# IN14.net
KiCad netlist of a schematic drawn in Altium Designer
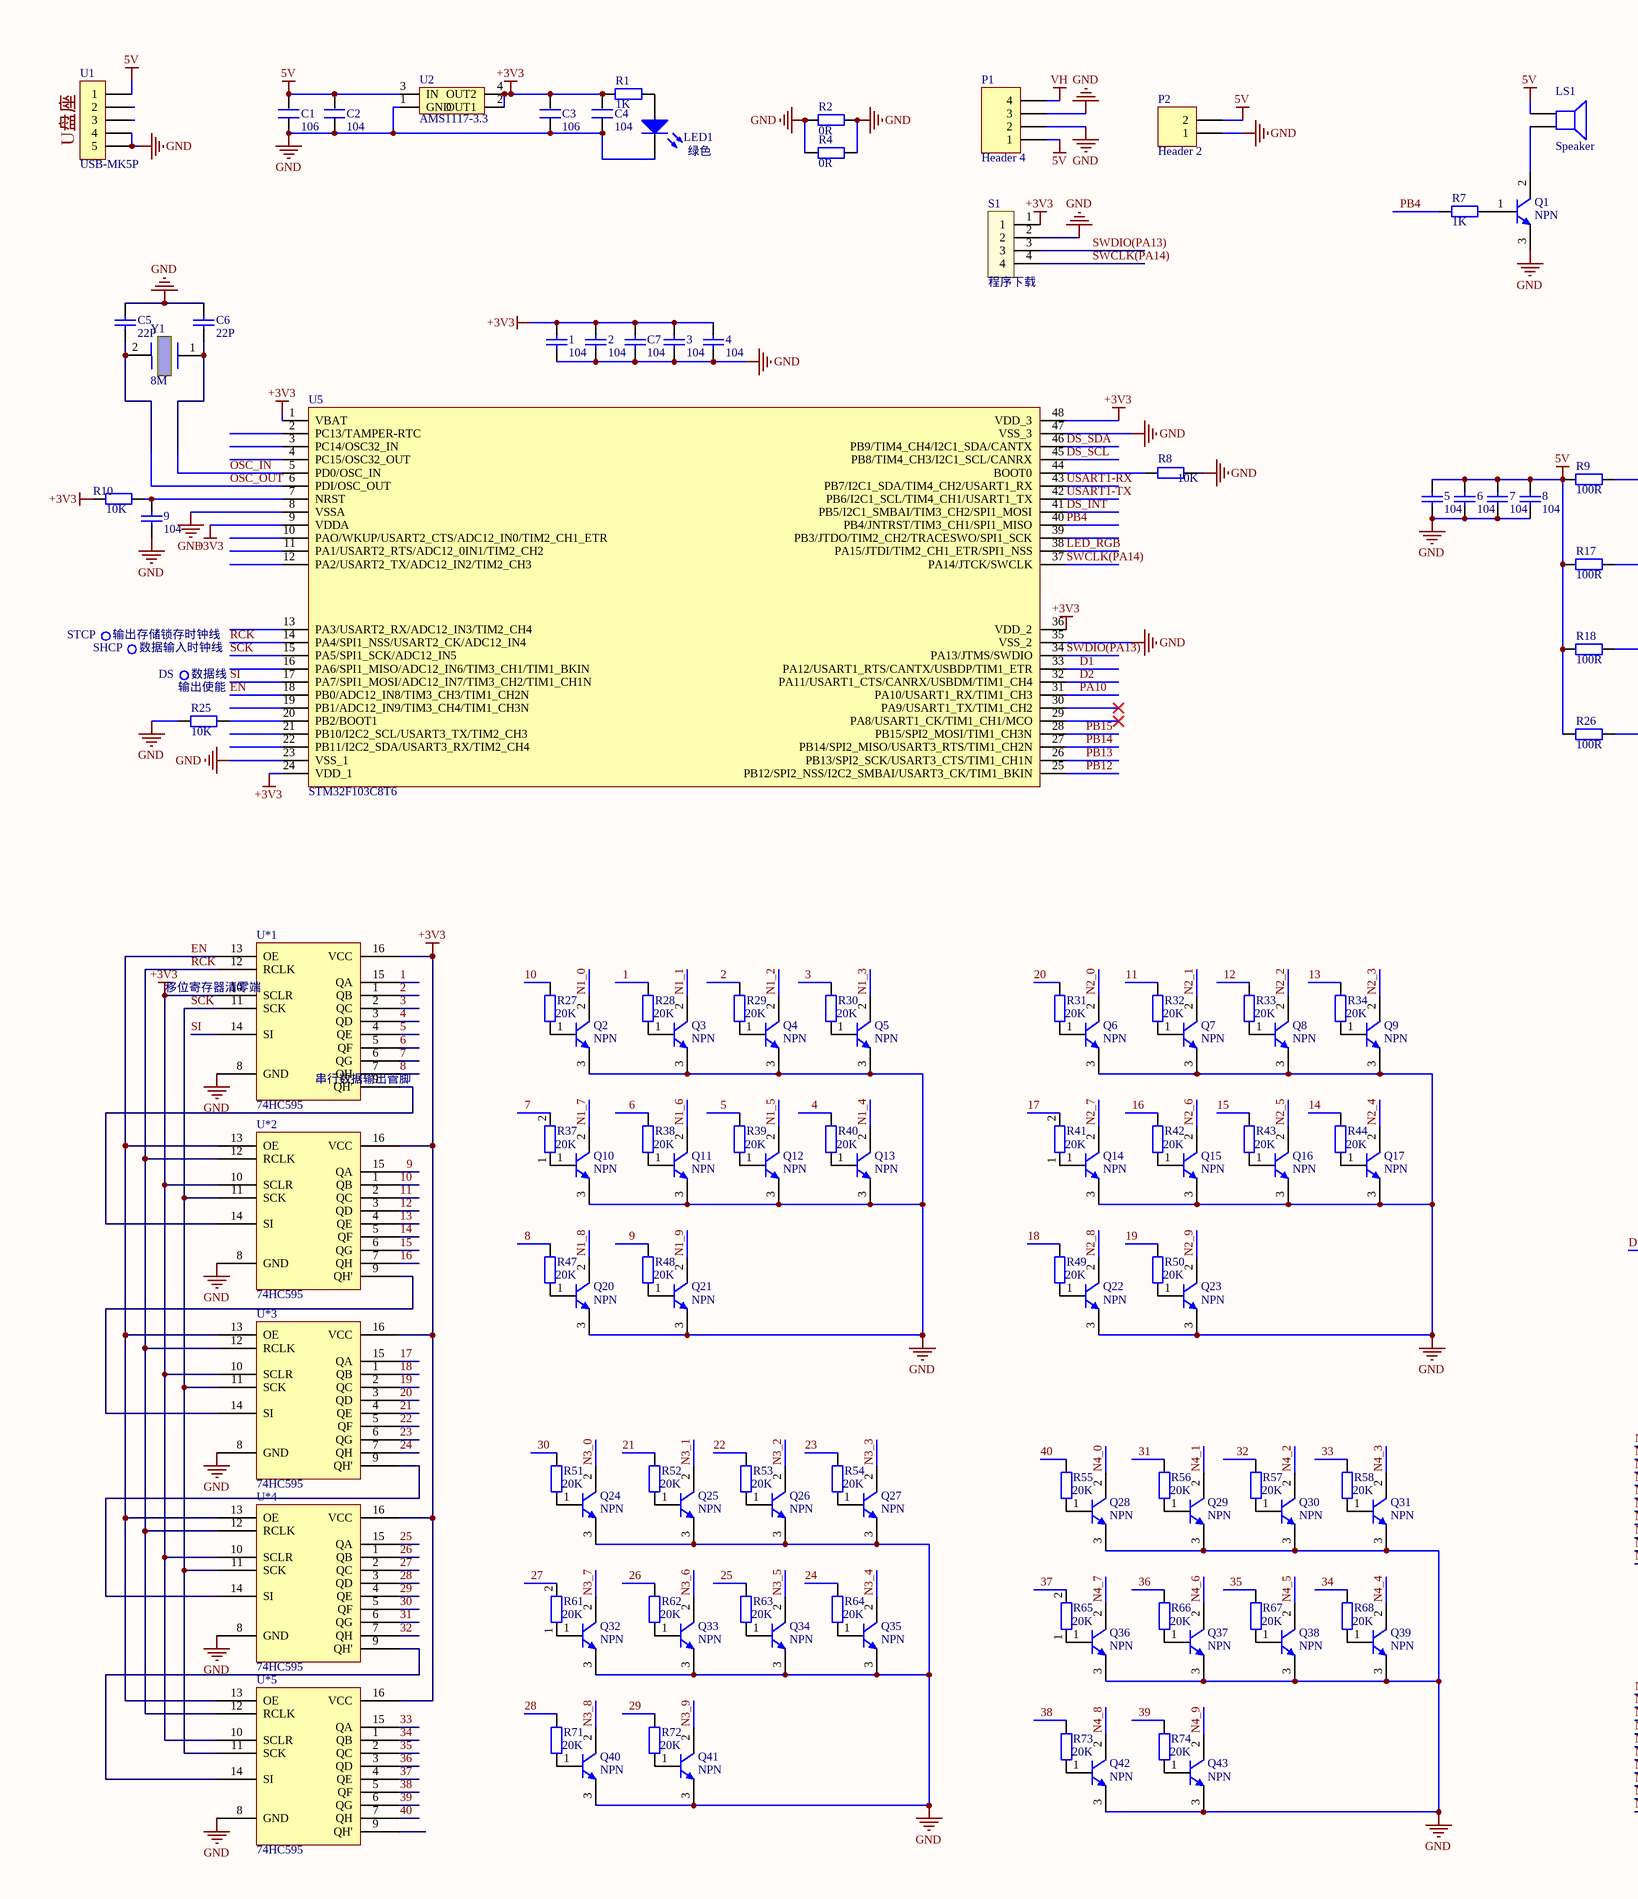
[diagram p0: IN14二灯.SchDoc, left]
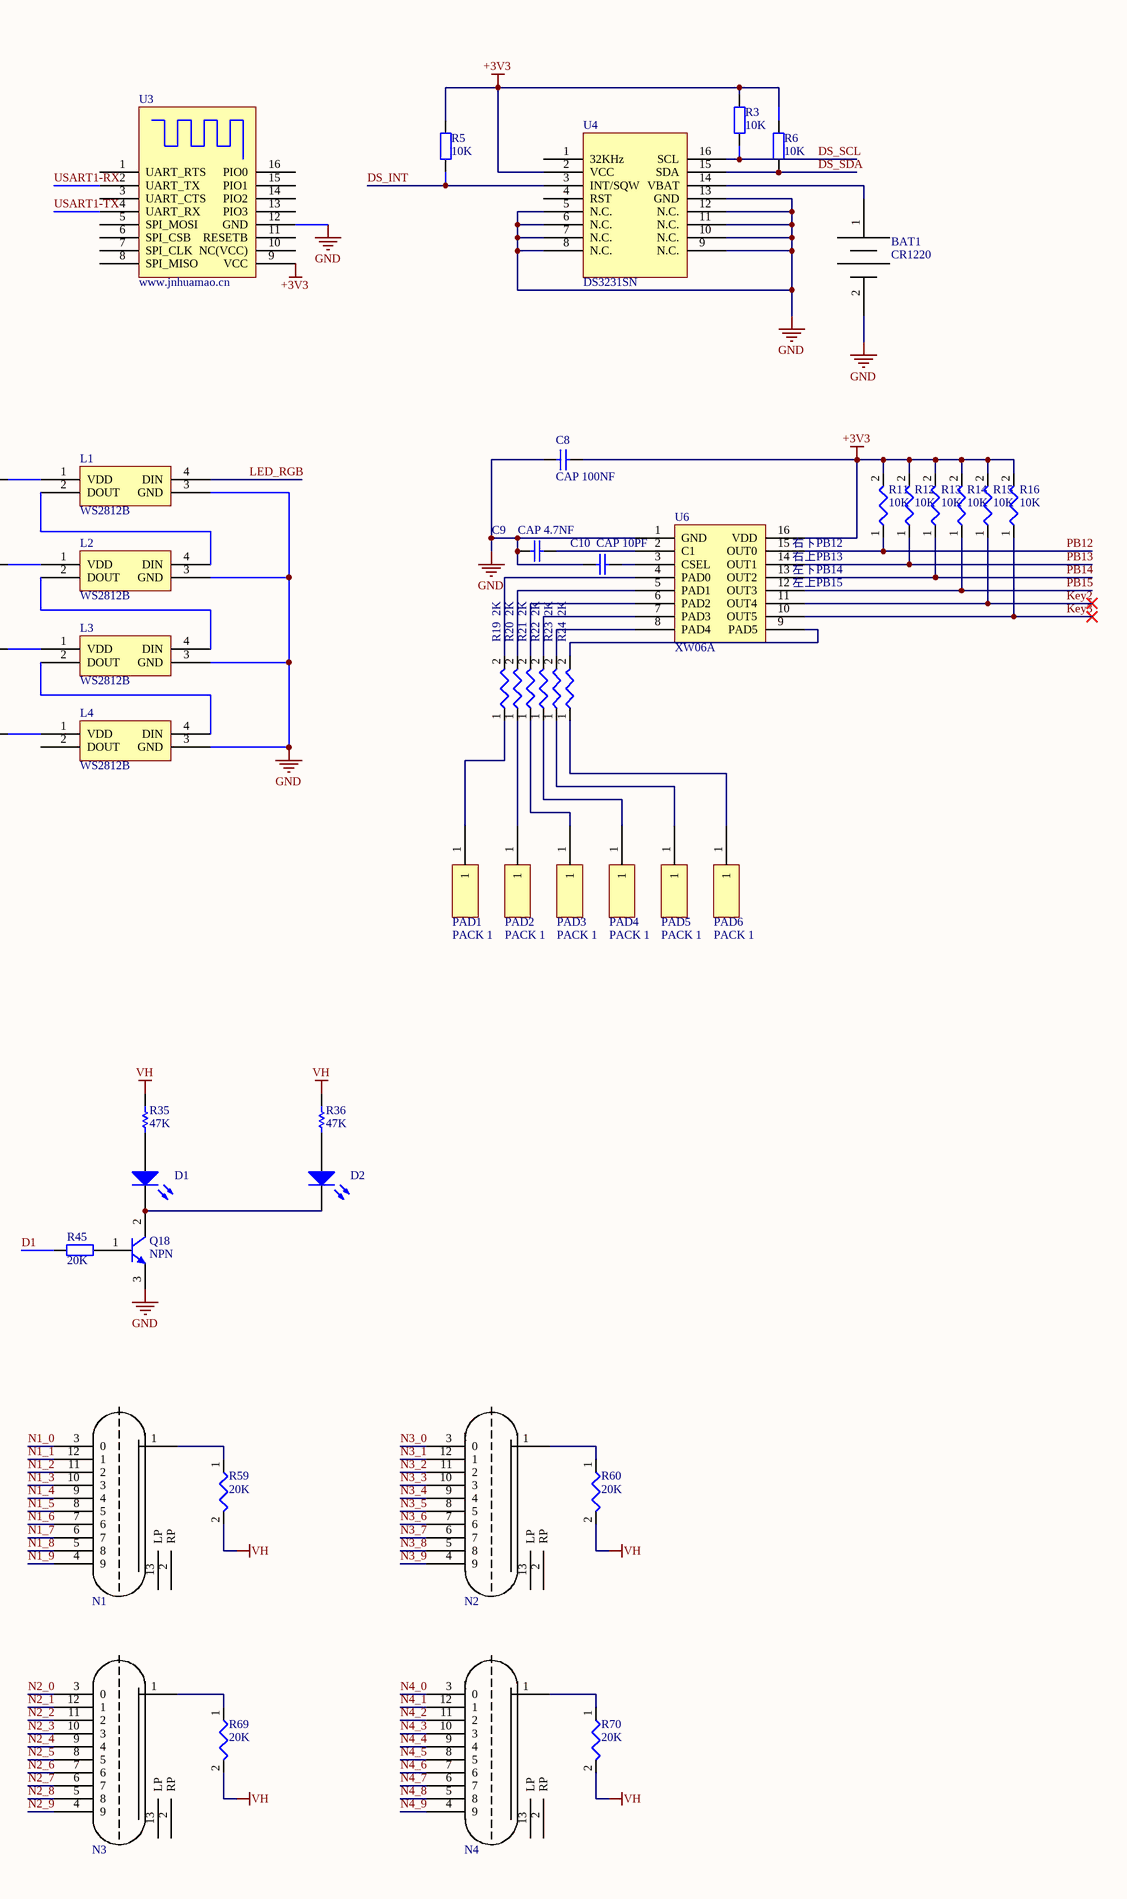
[diagram p1: IN14二灯.SchDoc, right]

(export (version "E")
  (design (tool "Eeschema 10.0.6"))
  (components
    (comp (ref "1")
      (value "104")
      (footprint "0603C")
      (description "无极性电容")
      (fields (field (name "PUBLISHER") "Altium Limited"))
      (libsource (lib "Fszhang") (part "Cap"))
    )
    (comp (ref "2")
      (value "104")
      (footprint "0603C")
      (description "无极性电容")
      (fields (field (name "PUBLISHER") "Altium Limited"))
      (libsource (lib "Fszhang") (part "Cap"))
    )
    (comp (ref "3")
      (value "104")
      (footprint "0603C")
      (description "无极性电容")
      (fields (field (name "PUBLISHER") "Altium Limited"))
      (libsource (lib "Fszhang") (part "Cap"))
    )
    (comp (ref "4")
      (value "104")
      (footprint "0603C")
      (description "无极性电容")
      (fields (field (name "PUBLISHER") "Altium Limited"))
      (libsource (lib "Fszhang") (part "Cap"))
    )
    (comp (ref "5")
      (value "104")
      (footprint "0603C")
      (description "无极性电容")
      (fields (field (name "PUBLISHER") "Altium Limited"))
      (libsource (lib "Fszhang") (part "Cap"))
    )
    (comp (ref "6")
      (value "104")
      (footprint "0603C")
      (description "无极性电容")
      (fields (field (name "PUBLISHER") "Altium Limited"))
      (libsource (lib "Fszhang") (part "Cap"))
    )
    (comp (ref "7")
      (value "104")
      (footprint "0603C")
      (description "无极性电容")
      (fields (field (name "PUBLISHER") "Altium Limited"))
      (libsource (lib "Fszhang") (part "Cap"))
    )
    (comp (ref "8")
      (value "104")
      (footprint "0603C")
      (description "无极性电容")
      (fields (field (name "PUBLISHER") "Altium Limited"))
      (libsource (lib "Fszhang") (part "Cap"))
    )
    (comp (ref "9")
      (value "104")
      (footprint "0603C")
      (description "无极性电容")
      (fields (field (name "PUBLISHER") "Altium Limited"))
      (libsource (lib "Fszhang") (part "Cap"))
    )
    (comp (ref "BAT1") (value "CR1220") (footprint "1220") (libsource (lib "LIGHT") (part "CR1220")))
    (comp (ref "C1") (value "106") (footprint "0805C") (libsource (lib "103驱动2") (part "C")))
    (comp (ref "C2") (value "104") (footprint "0603C") (libsource (lib "103驱动2") (part "C")))
    (comp (ref "C3") (value "106") (footprint "0805C") (libsource (lib "103驱动2") (part "C")))
    (comp (ref "C4") (value "104") (footprint "0603C") (libsource (lib "103驱动2") (part "C")))
    (comp (ref "C5")
      (value "22P")
      (footprint "0603C")
      (description "无极性电容")
      (fields (field (name "PUBLISHER") "Altium Limited"))
      (libsource (lib "Fszhang") (part "Cap"))
    )
    (comp (ref "C6")
      (value "22P")
      (footprint "0603C")
      (description "无极性电容")
      (fields (field (name "PUBLISHER") "Altium Limited"))
      (libsource (lib "Fszhang") (part "Cap"))
    )
    (comp (ref "C7")
      (value "104")
      (footprint "0603C")
      (description "无极性电容")
      (fields (field (name "PUBLISHER") "Altium Limited"))
      (libsource (lib "Fszhang") (part "Cap"))
    )
    (comp (ref "C8") (value "CAP 100NF") (footprint "0603C") (libsource (lib "LIGHT") (part "CAP ?F")))
    (comp (ref "C9") (value "CAP 4.7NF") (footprint "0603C") (libsource (lib "LIGHT") (part "CAP ?F")))
    (comp (ref "C10") (value "CAP 10PF") (footprint "0603C") (libsource (lib "LIGHT") (part "CAP ?F")))
    (comp (ref "D1")
      (value "LED0")
      (footprint "R38")
      (description "Typical INFRARED GaAs LED")
      (fields (field (name "PUBLISHER") "Altium Limited"))
      (libsource (lib "Miscellaneous Devices") (part "LED0"))
    )
    (comp (ref "D2")
      (value "LED0")
      (footprint "R38")
      (description "Typical INFRARED GaAs LED")
      (fields (field (name "PUBLISHER") "Altium Limited"))
      (libsource (lib "Miscellaneous Devices") (part "LED0"))
    )
    (comp (ref "L1") (value "WS2812B") (footprint "WS2812B") (libsource (lib "LIGHT") (part "WS2812B")))
    (comp (ref "L2") (value "WS2812B") (footprint "WS2812B") (libsource (lib "LIGHT") (part "WS2812B")))
    (comp (ref "L3") (value "WS2812B") (footprint "WS2812B") (libsource (lib "LIGHT") (part "WS2812B")))
    (comp (ref "L4") (value "WS2812B") (footprint "WS2812B") (libsource (lib "LIGHT") (part "WS2812B")))
    (comp (ref "LED1")
      (value "绿色")
      (footprint "LED_0805")
      (description "发光二极管")
      (fields (field (name "PUBLISHER") "Altium Limited"))
      (libsource (lib "Fszhang") (part "LED0"))
    )
    (comp (ref "LS1")
      (value "Speaker")
      (footprint "蜂鸣器9*9*5")
      (description "Loudspeaker")
      (fields (field (name "PUBLISHER") "Altium Limited"))
      (libsource (lib "Miscellaneous Devices") (part "Speaker"))
    )
    (comp (ref "N1") (value "IN_14") (footprint "IN14") (libsource (lib "LIGHT") (part "IN_14")))
    (comp (ref "N2") (value "IN_14") (footprint "IN14") (libsource (lib "LIGHT") (part "IN_14")))
    (comp (ref "N3") (value "IN_14") (footprint "IN14") (libsource (lib "LIGHT") (part "IN_14")))
    (comp (ref "N4") (value "IN_14") (footprint "IN14") (libsource (lib "LIGHT") (part "IN_14")))
    (comp (ref "P1")
      (value "Header 4")
      (footprint "XH2.54 4p贴片")
      (description "Header, 4-Pin")
      (fields (field (name "PUBLISHER") "Altium Limited"))
      (libsource (lib "Miscellaneous Connectors") (part "Header 4"))
    )
    (comp (ref "P2")
      (value "Header 2")
      (footprint "XH2.54-2P")
      (description "Header, 2-Pin")
      (fields (field (name "PUBLISHER") "Altium Limited"))
      (libsource (lib "Miscellaneous Connectors") (part "Header 2"))
    )
    (comp (ref "PAD1") (value "PACK 1") (footprint "PACK 1") (libsource (lib "LIGHT") (part "PACK 1")))
    (comp (ref "PAD2") (value "PACK 1") (footprint "PACK 1") (libsource (lib "LIGHT") (part "PACK 1")))
    (comp (ref "PAD3") (value "PACK 1") (footprint "PACK 1") (libsource (lib "LIGHT") (part "PACK 1")))
    (comp (ref "PAD4") (value "PACK 1") (footprint "PACK 1") (libsource (lib "LIGHT") (part "PACK 1")))
    (comp (ref "PAD5") (value "PACK 1") (footprint "PACK 1") (libsource (lib "LIGHT") (part "PACK 1")))
    (comp (ref "PAD6") (value "PACK 1") (footprint "PACK 1") (libsource (lib "LIGHT") (part "PACK 1")))
    (comp (ref "Q1")
      (value "NPN")
      (footprint "LC-SOT-23(SOT-23-3)")
      (description "NPN Bipolar Transistor")
      (fields (field (name "PUBLISHER") "Altium Limited"))
      (libsource (lib "Miscellaneous Devices") (part "NPN"))
    )
    (comp (ref "Q2")
      (value "NPN")
      (footprint "LC-SOT-23(SOT-23-3)")
      (description "NPN Bipolar Transistor")
      (fields (field (name "PUBLISHER") "Altium Limited"))
      (libsource (lib "Miscellaneous Devices") (part "NPN"))
    )
    (comp (ref "Q3")
      (value "NPN")
      (footprint "LC-SOT-23(SOT-23-3)")
      (description "NPN Bipolar Transistor")
      (fields (field (name "PUBLISHER") "Altium Limited"))
      (libsource (lib "Miscellaneous Devices") (part "NPN"))
    )
    (comp (ref "Q4")
      (value "NPN")
      (footprint "LC-SOT-23(SOT-23-3)")
      (description "NPN Bipolar Transistor")
      (fields (field (name "PUBLISHER") "Altium Limited"))
      (libsource (lib "Miscellaneous Devices") (part "NPN"))
    )
    (comp (ref "Q5")
      (value "NPN")
      (footprint "LC-SOT-23(SOT-23-3)")
      (description "NPN Bipolar Transistor")
      (fields (field (name "PUBLISHER") "Altium Limited"))
      (libsource (lib "Miscellaneous Devices") (part "NPN"))
    )
    (comp (ref "Q6")
      (value "NPN")
      (footprint "LC-SOT-23(SOT-23-3)")
      (description "NPN Bipolar Transistor")
      (fields (field (name "PUBLISHER") "Altium Limited"))
      (libsource (lib "Miscellaneous Devices") (part "NPN"))
    )
    (comp (ref "Q7")
      (value "NPN")
      (footprint "LC-SOT-23(SOT-23-3)")
      (description "NPN Bipolar Transistor")
      (fields (field (name "PUBLISHER") "Altium Limited"))
      (libsource (lib "Miscellaneous Devices") (part "NPN"))
    )
    (comp (ref "Q8")
      (value "NPN")
      (footprint "LC-SOT-23(SOT-23-3)")
      (description "NPN Bipolar Transistor")
      (fields (field (name "PUBLISHER") "Altium Limited"))
      (libsource (lib "Miscellaneous Devices") (part "NPN"))
    )
    (comp (ref "Q9")
      (value "NPN")
      (footprint "LC-SOT-23(SOT-23-3)")
      (description "NPN Bipolar Transistor")
      (fields (field (name "PUBLISHER") "Altium Limited"))
      (libsource (lib "Miscellaneous Devices") (part "NPN"))
    )
    (comp (ref "Q10")
      (value "NPN")
      (footprint "LC-SOT-23(SOT-23-3)")
      (description "NPN Bipolar Transistor")
      (fields (field (name "PUBLISHER") "Altium Limited"))
      (libsource (lib "Miscellaneous Devices") (part "NPN"))
    )
    (comp (ref "Q11")
      (value "NPN")
      (footprint "LC-SOT-23(SOT-23-3)")
      (description "NPN Bipolar Transistor")
      (fields (field (name "PUBLISHER") "Altium Limited"))
      (libsource (lib "Miscellaneous Devices") (part "NPN"))
    )
    (comp (ref "Q12")
      (value "NPN")
      (footprint "LC-SOT-23(SOT-23-3)")
      (description "NPN Bipolar Transistor")
      (fields (field (name "PUBLISHER") "Altium Limited"))
      (libsource (lib "Miscellaneous Devices") (part "NPN"))
    )
    (comp (ref "Q13")
      (value "NPN")
      (footprint "LC-SOT-23(SOT-23-3)")
      (description "NPN Bipolar Transistor")
      (fields (field (name "PUBLISHER") "Altium Limited"))
      (libsource (lib "Miscellaneous Devices") (part "NPN"))
    )
    (comp (ref "Q14")
      (value "NPN")
      (footprint "LC-SOT-23(SOT-23-3)")
      (description "NPN Bipolar Transistor")
      (fields (field (name "PUBLISHER") "Altium Limited"))
      (libsource (lib "Miscellaneous Devices") (part "NPN"))
    )
    (comp (ref "Q15")
      (value "NPN")
      (footprint "LC-SOT-23(SOT-23-3)")
      (description "NPN Bipolar Transistor")
      (fields (field (name "PUBLISHER") "Altium Limited"))
      (libsource (lib "Miscellaneous Devices") (part "NPN"))
    )
    (comp (ref "Q16")
      (value "NPN")
      (footprint "LC-SOT-23(SOT-23-3)")
      (description "NPN Bipolar Transistor")
      (fields (field (name "PUBLISHER") "Altium Limited"))
      (libsource (lib "Miscellaneous Devices") (part "NPN"))
    )
    (comp (ref "Q17")
      (value "NPN")
      (footprint "LC-SOT-23(SOT-23-3)")
      (description "NPN Bipolar Transistor")
      (fields (field (name "PUBLISHER") "Altium Limited"))
      (libsource (lib "Miscellaneous Devices") (part "NPN"))
    )
    (comp (ref "Q18")
      (value "NPN")
      (footprint "LC-SOT-23(SOT-23-3)")
      (description "NPN Bipolar Transistor")
      (fields (field (name "PUBLISHER") "Altium Limited"))
      (libsource (lib "Miscellaneous Devices") (part "NPN"))
    )
    (comp (ref "Q20")
      (value "NPN")
      (footprint "LC-SOT-23(SOT-23-3)")
      (description "NPN Bipolar Transistor")
      (fields (field (name "PUBLISHER") "Altium Limited"))
      (libsource (lib "Miscellaneous Devices") (part "NPN"))
    )
    (comp (ref "Q21")
      (value "NPN")
      (footprint "LC-SOT-23(SOT-23-3)")
      (description "NPN Bipolar Transistor")
      (fields (field (name "PUBLISHER") "Altium Limited"))
      (libsource (lib "Miscellaneous Devices") (part "NPN"))
    )
    (comp (ref "Q22")
      (value "NPN")
      (footprint "LC-SOT-23(SOT-23-3)")
      (description "NPN Bipolar Transistor")
      (fields (field (name "PUBLISHER") "Altium Limited"))
      (libsource (lib "Miscellaneous Devices") (part "NPN"))
    )
    (comp (ref "Q23")
      (value "NPN")
      (footprint "LC-SOT-23(SOT-23-3)")
      (description "NPN Bipolar Transistor")
      (fields (field (name "PUBLISHER") "Altium Limited"))
      (libsource (lib "Miscellaneous Devices") (part "NPN"))
    )
    (comp (ref "Q24")
      (value "NPN")
      (footprint "LC-SOT-23(SOT-23-3)")
      (description "NPN Bipolar Transistor")
      (fields (field (name "PUBLISHER") "Altium Limited"))
      (libsource (lib "Miscellaneous Devices") (part "NPN"))
    )
    (comp (ref "Q25")
      (value "NPN")
      (footprint "LC-SOT-23(SOT-23-3)")
      (description "NPN Bipolar Transistor")
      (fields (field (name "PUBLISHER") "Altium Limited"))
      (libsource (lib "Miscellaneous Devices") (part "NPN"))
    )
    (comp (ref "Q26")
      (value "NPN")
      (footprint "LC-SOT-23(SOT-23-3)")
      (description "NPN Bipolar Transistor")
      (fields (field (name "PUBLISHER") "Altium Limited"))
      (libsource (lib "Miscellaneous Devices") (part "NPN"))
    )
    (comp (ref "Q27")
      (value "NPN")
      (footprint "LC-SOT-23(SOT-23-3)")
      (description "NPN Bipolar Transistor")
      (fields (field (name "PUBLISHER") "Altium Limited"))
      (libsource (lib "Miscellaneous Devices") (part "NPN"))
    )
    (comp (ref "Q28")
      (value "NPN")
      (footprint "LC-SOT-23(SOT-23-3)")
      (description "NPN Bipolar Transistor")
      (fields (field (name "PUBLISHER") "Altium Limited"))
      (libsource (lib "Miscellaneous Devices") (part "NPN"))
    )
    (comp (ref "Q29")
      (value "NPN")
      (footprint "LC-SOT-23(SOT-23-3)")
      (description "NPN Bipolar Transistor")
      (fields (field (name "PUBLISHER") "Altium Limited"))
      (libsource (lib "Miscellaneous Devices") (part "NPN"))
    )
    (comp (ref "Q30")
      (value "NPN")
      (footprint "LC-SOT-23(SOT-23-3)")
      (description "NPN Bipolar Transistor")
      (fields (field (name "PUBLISHER") "Altium Limited"))
      (libsource (lib "Miscellaneous Devices") (part "NPN"))
    )
    (comp (ref "Q31")
      (value "NPN")
      (footprint "LC-SOT-23(SOT-23-3)")
      (description "NPN Bipolar Transistor")
      (fields (field (name "PUBLISHER") "Altium Limited"))
      (libsource (lib "Miscellaneous Devices") (part "NPN"))
    )
    (comp (ref "Q32")
      (value "NPN")
      (footprint "LC-SOT-23(SOT-23-3)")
      (description "NPN Bipolar Transistor")
      (fields (field (name "PUBLISHER") "Altium Limited"))
      (libsource (lib "Miscellaneous Devices") (part "NPN"))
    )
    (comp (ref "Q33")
      (value "NPN")
      (footprint "LC-SOT-23(SOT-23-3)")
      (description "NPN Bipolar Transistor")
      (fields (field (name "PUBLISHER") "Altium Limited"))
      (libsource (lib "Miscellaneous Devices") (part "NPN"))
    )
    (comp (ref "Q34")
      (value "NPN")
      (footprint "LC-SOT-23(SOT-23-3)")
      (description "NPN Bipolar Transistor")
      (fields (field (name "PUBLISHER") "Altium Limited"))
      (libsource (lib "Miscellaneous Devices") (part "NPN"))
    )
    (comp (ref "Q35")
      (value "NPN")
      (footprint "LC-SOT-23(SOT-23-3)")
      (description "NPN Bipolar Transistor")
      (fields (field (name "PUBLISHER") "Altium Limited"))
      (libsource (lib "Miscellaneous Devices") (part "NPN"))
    )
    (comp (ref "Q36")
      (value "NPN")
      (footprint "LC-SOT-23(SOT-23-3)")
      (description "NPN Bipolar Transistor")
      (fields (field (name "PUBLISHER") "Altium Limited"))
      (libsource (lib "Miscellaneous Devices") (part "NPN"))
    )
    (comp (ref "Q37")
      (value "NPN")
      (footprint "LC-SOT-23(SOT-23-3)")
      (description "NPN Bipolar Transistor")
      (fields (field (name "PUBLISHER") "Altium Limited"))
      (libsource (lib "Miscellaneous Devices") (part "NPN"))
    )
    (comp (ref "Q38")
      (value "NPN")
      (footprint "LC-SOT-23(SOT-23-3)")
      (description "NPN Bipolar Transistor")
      (fields (field (name "PUBLISHER") "Altium Limited"))
      (libsource (lib "Miscellaneous Devices") (part "NPN"))
    )
    (comp (ref "Q39")
      (value "NPN")
      (footprint "LC-SOT-23(SOT-23-3)")
      (description "NPN Bipolar Transistor")
      (fields (field (name "PUBLISHER") "Altium Limited"))
      (libsource (lib "Miscellaneous Devices") (part "NPN"))
    )
    (comp (ref "Q40")
      (value "NPN")
      (footprint "LC-SOT-23(SOT-23-3)")
      (description "NPN Bipolar Transistor")
      (fields (field (name "PUBLISHER") "Altium Limited"))
      (libsource (lib "Miscellaneous Devices") (part "NPN"))
    )
    (comp (ref "Q41")
      (value "NPN")
      (footprint "LC-SOT-23(SOT-23-3)")
      (description "NPN Bipolar Transistor")
      (fields (field (name "PUBLISHER") "Altium Limited"))
      (libsource (lib "Miscellaneous Devices") (part "NPN"))
    )
    (comp (ref "Q42")
      (value "NPN")
      (footprint "LC-SOT-23(SOT-23-3)")
      (description "NPN Bipolar Transistor")
      (fields (field (name "PUBLISHER") "Altium Limited"))
      (libsource (lib "Miscellaneous Devices") (part "NPN"))
    )
    (comp (ref "Q43")
      (value "NPN")
      (footprint "LC-SOT-23(SOT-23-3)")
      (description "NPN Bipolar Transistor")
      (fields (field (name "PUBLISHER") "Altium Limited"))
      (libsource (lib "Miscellaneous Devices") (part "NPN"))
    )
    (comp (ref "R1")
      (value "1K")
      (footprint "0603R")
      (description "贴片电阻")
      (fields (field (name "PUBLISHER") "Altium Limited"))
      (libsource (lib "") (part "Res1_2"))
    )
    (comp (ref "R2")
      (value "0R")
      (footprint "0603R")
      (description "贴片电阻")
      (fields (field (name "PUBLISHER") "Altium Limited"))
      (libsource (lib "") (part "Res1_1"))
    )
    (comp (ref "R3")
      (value "10K")
      (footprint "0603R")
      (description "贴片电阻")
      (fields (field (name "PUBLISHER") "Altium Limited"))
      (libsource (lib "Fszhang") (part "Res1"))
    )
    (comp (ref "R4")
      (value "0R")
      (footprint "0603R")
      (description "贴片电阻")
      (fields (field (name "PUBLISHER") "Altium Limited"))
      (libsource (lib "") (part "Res1_1"))
    )
    (comp (ref "R5")
      (value "10K")
      (footprint "0603R")
      (description "贴片电阻")
      (fields (field (name "PUBLISHER") "Altium Limited"))
      (libsource (lib "Fszhang") (part "Res1"))
    )
    (comp (ref "R6")
      (value "10K")
      (footprint "0603R")
      (description "贴片电阻")
      (fields (field (name "PUBLISHER") "Altium Limited"))
      (libsource (lib "Fszhang") (part "Res1"))
    )
    (comp (ref "R7")
      (value "1K")
      (footprint "0603R")
      (description "贴片电阻")
      (fields (field (name "PUBLISHER") "Altium Limited"))
      (libsource (lib "") (part "Res1_1"))
    )
    (comp (ref "R8")
      (value "10K")
      (footprint "0603R")
      (description "贴片电阻")
      (fields (field (name "PUBLISHER") "Altium Limited"))
      (libsource (lib "") (part "Res1_1"))
    )
    (comp (ref "R9")
      (value "100R")
      (footprint "0603R")
      (description "贴片电阻")
      (fields (field (name "PUBLISHER") "Altium Limited"))
      (libsource (lib "") (part "Res1_2"))
    )
    (comp (ref "R10")
      (value "10K")
      (footprint "0603R")
      (description "贴片电阻")
      (fields (field (name "PUBLISHER") "Altium Limited"))
      (libsource (lib "") (part "Res1_1"))
    )
    (comp (ref "R11") (value "10K") (footprint "0603R") (libsource (lib "LIGHT") (part "?K")))
    (comp (ref "R12") (value "10K") (footprint "0603R") (libsource (lib "LIGHT") (part "?K")))
    (comp (ref "R13") (value "10K") (footprint "0603R") (libsource (lib "LIGHT") (part "?K")))
    (comp (ref "R14") (value "10K") (footprint "0603R") (libsource (lib "LIGHT") (part "?K")))
    (comp (ref "R15") (value "10K") (footprint "0603R") (libsource (lib "LIGHT") (part "?K")))
    (comp (ref "R16") (value "10K") (footprint "0603R") (libsource (lib "LIGHT") (part "?K")))
    (comp (ref "R17")
      (value "100R")
      (footprint "0603R")
      (description "贴片电阻")
      (fields (field (name "PUBLISHER") "Altium Limited"))
      (libsource (lib "") (part "Res1_2"))
    )
    (comp (ref "R18")
      (value "100R")
      (footprint "0603R")
      (description "贴片电阻")
      (fields (field (name "PUBLISHER") "Altium Limited"))
      (libsource (lib "") (part "Res1_2"))
    )
    (comp (ref "R19") (value "2K") (footprint "0603R") (libsource (lib "LIGHT") (part "?K")))
    (comp (ref "R20") (value "2K") (footprint "0603R") (libsource (lib "LIGHT") (part "?K")))
    (comp (ref "R21") (value "2K") (footprint "0603R") (libsource (lib "LIGHT") (part "?K")))
    (comp (ref "R22") (value "2K") (footprint "0603R") (libsource (lib "LIGHT") (part "?K")))
    (comp (ref "R23") (value "2K") (footprint "0603R") (libsource (lib "LIGHT") (part "?K")))
    (comp (ref "R24") (value "2K") (footprint "0603R") (libsource (lib "LIGHT") (part "?K")))
    (comp (ref "R25")
      (value "10K")
      (footprint "0603R")
      (description "贴片电阻")
      (fields (field (name "PUBLISHER") "Altium Limited"))
      (libsource (lib "") (part "Res1_1"))
    )
    (comp (ref "R26")
      (value "100R")
      (footprint "0603R")
      (description "贴片电阻")
      (fields (field (name "PUBLISHER") "Altium Limited"))
      (libsource (lib "") (part "Res1_2"))
    )
    (comp (ref "R27")
      (value "20K")
      (footprint "0603R")
      (description "贴片电阻")
      (fields (field (name "PUBLISHER") "Altium Limited"))
      (libsource (lib "Fszhang") (part "Res1"))
    )
    (comp (ref "R28")
      (value "20K")
      (footprint "0603R")
      (description "贴片电阻")
      (fields (field (name "PUBLISHER") "Altium Limited"))
      (libsource (lib "Fszhang") (part "Res1"))
    )
    (comp (ref "R29")
      (value "20K")
      (footprint "0603R")
      (description "贴片电阻")
      (fields (field (name "PUBLISHER") "Altium Limited"))
      (libsource (lib "Fszhang") (part "Res1"))
    )
    (comp (ref "R30")
      (value "20K")
      (footprint "0603R")
      (description "贴片电阻")
      (fields (field (name "PUBLISHER") "Altium Limited"))
      (libsource (lib "Fszhang") (part "Res1"))
    )
    (comp (ref "R31")
      (value "20K")
      (footprint "0603R")
      (description "贴片电阻")
      (fields (field (name "PUBLISHER") "Altium Limited"))
      (libsource (lib "Fszhang") (part "Res1"))
    )
    (comp (ref "R32")
      (value "20K")
      (footprint "0603R")
      (description "贴片电阻")
      (fields (field (name "PUBLISHER") "Altium Limited"))
      (libsource (lib "Fszhang") (part "Res1"))
    )
    (comp (ref "R33")
      (value "20K")
      (footprint "0603R")
      (description "贴片电阻")
      (fields (field (name "PUBLISHER") "Altium Limited"))
      (libsource (lib "Fszhang") (part "Res1"))
    )
    (comp (ref "R34")
      (value "20K")
      (footprint "0603R")
      (description "贴片电阻")
      (fields (field (name "PUBLISHER") "Altium Limited"))
      (libsource (lib "Fszhang") (part "Res1"))
    )
    (comp (ref "R35")
      (value "47K")
      (footprint "0805C")
      (description "Resistor")
      (fields (field (name "Comment") "Res1") (field (name "PUBLISHER") "Altium Limited"))
      (libsource (lib "Miscellaneous Devices") (part "Res1"))
    )
    (comp (ref "R36")
      (value "47K")
      (footprint "0805C")
      (description "Resistor")
      (fields (field (name "Comment") "Res1") (field (name "PUBLISHER") "Altium Limited"))
      (libsource (lib "Miscellaneous Devices") (part "Res1"))
    )
    (comp (ref "R37")
      (value "20K")
      (footprint "0603R")
      (description "贴片电阻")
      (fields (field (name "PUBLISHER") "Altium Limited"))
      (libsource (lib "") (part "Res1_3"))
    )
    (comp (ref "R38")
      (value "20K")
      (footprint "0603R")
      (description "贴片电阻")
      (fields (field (name "PUBLISHER") "Altium Limited"))
      (libsource (lib "Fszhang") (part "Res1"))
    )
    (comp (ref "R39")
      (value "20K")
      (footprint "0603R")
      (description "贴片电阻")
      (fields (field (name "PUBLISHER") "Altium Limited"))
      (libsource (lib "Fszhang") (part "Res1"))
    )
    (comp (ref "R40")
      (value "20K")
      (footprint "0603R")
      (description "贴片电阻")
      (fields (field (name "PUBLISHER") "Altium Limited"))
      (libsource (lib "Fszhang") (part "Res1"))
    )
    (comp (ref "R41")
      (value "20K")
      (footprint "0603R")
      (description "贴片电阻")
      (fields (field (name "PUBLISHER") "Altium Limited"))
      (libsource (lib "") (part "Res1_3"))
    )
    (comp (ref "R42")
      (value "20K")
      (footprint "0603R")
      (description "贴片电阻")
      (fields (field (name "PUBLISHER") "Altium Limited"))
      (libsource (lib "Fszhang") (part "Res1"))
    )
    (comp (ref "R43")
      (value "20K")
      (footprint "0603R")
      (description "贴片电阻")
      (fields (field (name "PUBLISHER") "Altium Limited"))
      (libsource (lib "Fszhang") (part "Res1"))
    )
    (comp (ref "R44")
      (value "20K")
      (footprint "0603R")
      (description "贴片电阻")
      (fields (field (name "PUBLISHER") "Altium Limited"))
      (libsource (lib "Fszhang") (part "Res1"))
    )
    (comp (ref "R45")
      (value "20K")
      (footprint "0603R")
      (description "贴片电阻")
      (fields (field (name "PUBLISHER") "Altium Limited"))
      (libsource (lib "") (part "Res1_2"))
    )
    (comp (ref "R47")
      (value "20K")
      (footprint "0603R")
      (description "贴片电阻")
      (fields (field (name "PUBLISHER") "Altium Limited"))
      (libsource (lib "Fszhang") (part "Res1"))
    )
    (comp (ref "R48")
      (value "20K")
      (footprint "0603R")
      (description "贴片电阻")
      (fields (field (name "PUBLISHER") "Altium Limited"))
      (libsource (lib "Fszhang") (part "Res1"))
    )
    (comp (ref "R49")
      (value "20K")
      (footprint "0603R")
      (description "贴片电阻")
      (fields (field (name "PUBLISHER") "Altium Limited"))
      (libsource (lib "Fszhang") (part "Res1"))
    )
    (comp (ref "R50")
      (value "20K")
      (footprint "0603R")
      (description "贴片电阻")
      (fields (field (name "PUBLISHER") "Altium Limited"))
      (libsource (lib "Fszhang") (part "Res1"))
    )
    (comp (ref "R51")
      (value "20K")
      (footprint "0603R")
      (description "贴片电阻")
      (fields (field (name "PUBLISHER") "Altium Limited"))
      (libsource (lib "Fszhang") (part "Res1"))
    )
    (comp (ref "R52")
      (value "20K")
      (footprint "0603R")
      (description "贴片电阻")
      (fields (field (name "PUBLISHER") "Altium Limited"))
      (libsource (lib "Fszhang") (part "Res1"))
    )
    (comp (ref "R53")
      (value "20K")
      (footprint "0603R")
      (description "贴片电阻")
      (fields (field (name "PUBLISHER") "Altium Limited"))
      (libsource (lib "Fszhang") (part "Res1"))
    )
    (comp (ref "R54")
      (value "20K")
      (footprint "0603R")
      (description "贴片电阻")
      (fields (field (name "PUBLISHER") "Altium Limited"))
      (libsource (lib "Fszhang") (part "Res1"))
    )
    (comp (ref "R55")
      (value "20K")
      (footprint "0603R")
      (description "贴片电阻")
      (fields (field (name "PUBLISHER") "Altium Limited"))
      (libsource (lib "Fszhang") (part "Res1"))
    )
    (comp (ref "R56")
      (value "20K")
      (footprint "0603R")
      (description "贴片电阻")
      (fields (field (name "PUBLISHER") "Altium Limited"))
      (libsource (lib "Fszhang") (part "Res1"))
    )
    (comp (ref "R57")
      (value "20K")
      (footprint "0603R")
      (description "贴片电阻")
      (fields (field (name "PUBLISHER") "Altium Limited"))
      (libsource (lib "Fszhang") (part "Res1"))
    )
    (comp (ref "R58")
      (value "20K")
      (footprint "0603R")
      (description "贴片电阻")
      (fields (field (name "PUBLISHER") "Altium Limited"))
      (libsource (lib "Fszhang") (part "Res1"))
    )
    (comp (ref "R59") (value "20K") (footprint "0805C") (libsource (lib "LIGHT") (part "?K")))
    (comp (ref "R60") (value "20K") (footprint "0805C") (libsource (lib "LIGHT") (part "?K")))
    (comp (ref "R61")
      (value "20K")
      (footprint "0603R")
      (description "贴片电阻")
      (fields (field (name "PUBLISHER") "Altium Limited"))
      (libsource (lib "") (part "Res1_3"))
    )
    (comp (ref "R62")
      (value "20K")
      (footprint "0603R")
      (description "贴片电阻")
      (fields (field (name "PUBLISHER") "Altium Limited"))
      (libsource (lib "Fszhang") (part "Res1"))
    )
    (comp (ref "R63")
      (value "20K")
      (footprint "0603R")
      (description "贴片电阻")
      (fields (field (name "PUBLISHER") "Altium Limited"))
      (libsource (lib "Fszhang") (part "Res1"))
    )
    (comp (ref "R64")
      (value "20K")
      (footprint "0603R")
      (description "贴片电阻")
      (fields (field (name "PUBLISHER") "Altium Limited"))
      (libsource (lib "Fszhang") (part "Res1"))
    )
    (comp (ref "R65")
      (value "20K")
      (footprint "0603R")
      (description "贴片电阻")
      (fields (field (name "PUBLISHER") "Altium Limited"))
      (libsource (lib "") (part "Res1_3"))
    )
    (comp (ref "R66")
      (value "20K")
      (footprint "0603R")
      (description "贴片电阻")
      (fields (field (name "PUBLISHER") "Altium Limited"))
      (libsource (lib "Fszhang") (part "Res1"))
    )
    (comp (ref "R67")
      (value "20K")
      (footprint "0603R")
      (description "贴片电阻")
      (fields (field (name "PUBLISHER") "Altium Limited"))
      (libsource (lib "Fszhang") (part "Res1"))
    )
    (comp (ref "R68")
      (value "20K")
      (footprint "0603R")
      (description "贴片电阻")
      (fields (field (name "PUBLISHER") "Altium Limited"))
      (libsource (lib "Fszhang") (part "Res1"))
    )
    (comp (ref "R69") (value "20K") (footprint "0805C") (libsource (lib "LIGHT") (part "?K")))
    (comp (ref "R70") (value "20K") (footprint "0805C") (libsource (lib "LIGHT") (part "?K")))
    (comp (ref "R71")
      (value "20K")
      (footprint "0603R")
      (description "贴片电阻")
      (fields (field (name "PUBLISHER") "Altium Limited"))
      (libsource (lib "Fszhang") (part "Res1"))
    )
    (comp (ref "R72")
      (value "20K")
      (footprint "0603R")
      (description "贴片电阻")
      (fields (field (name "PUBLISHER") "Altium Limited"))
      (libsource (lib "Fszhang") (part "Res1"))
    )
    (comp (ref "R73")
      (value "20K")
      (footprint "0603R")
      (description "贴片电阻")
      (fields (field (name "PUBLISHER") "Altium Limited"))
      (libsource (lib "Fszhang") (part "Res1"))
    )
    (comp (ref "R74")
      (value "20K")
      (footprint "0603R")
      (description "贴片电阻")
      (fields (field (name "PUBLISHER") "Altium Limited"))
      (libsource (lib "Fszhang") (part "Res1"))
    )
    (comp (ref "S1") (value "程序下载") (footprint "HDR1X4") (libsource (lib "ZBC123Schlib1") (part "S-4")))
    (comp (ref "U*1")
      (value "74HC595")
      (footprint "SOP16_M")
      (libsource (lib "74HC595") (part "Component_1"))
    )
    (comp (ref "U*2")
      (value "74HC595")
      (footprint "SOP16_M")
      (libsource (lib "74HC595") (part "Component_1"))
    )
    (comp (ref "U*3")
      (value "74HC595")
      (footprint "SOP16_M")
      (libsource (lib "74HC595") (part "Component_1"))
    )
    (comp (ref "U*4")
      (value "74HC595")
      (footprint "SOP16_M")
      (libsource (lib "74HC595") (part "Component_1"))
    )
    (comp (ref "U*5")
      (value "74HC595")
      (footprint "SOP16_M")
      (libsource (lib "74HC595") (part "Component_1"))
    )
    (comp (ref "U1")
      (value "USB-MK5P")
      (footprint "USB-MK5P")
      (description "Connector")
      (libsource (lib "*") (part "CON5"))
    )
    (comp (ref "U2")
      (value "AMS1117-3.3")
      (footprint "LC-SOT-223 (1117)")
      (libsource (lib "WARSHIP") (part "AMS1117"))
    )
    (comp (ref "U3")
      (value "www.jnhuamao.cn")
      (footprint "HM-05_06_07_11")
      (description "HM bluetooth module HM-05,HM-06,HM-07, HM-11")
      (libsource (lib "HMSoft") (part "HM_05_06_07_11"))
    )
    (comp (ref "U4")
      (value "DS3231SN")
      (footprint "LC-SOP-16_300mil")
      (libsource (lib "LIGHT") (part "DS3231SN"))
    )
    (comp (ref "U5")
      (value "STM32F103C8T6")
      (footprint "LQFP-48_M")
      (libsource (lib "WARSHIP") (part "STM32F103C8T6"))
    )
    (comp (ref "U6") (value "XW06A") (footprint "SO-16_L") (libsource (lib "LIGHT") (part "XW06A")))
    (comp (ref "Y1") (value "8M") (footprint "Y-XTAL T") (libsource (lib "ZBC124Schlib1") (part "JZ")))
  )
  (nets
    (net (code "1") (name "+3V3") (class "Default")
      (node (ref "1") (pin "2") (pinfunction "2_2") (pintype "passive"))
      (node (ref "2") (pin "2") (pinfunction "2_2") (pintype "passive"))
      (node (ref "3") (pin "2") (pinfunction "2_2") (pintype "passive"))
      (node (ref "4") (pin "2") (pinfunction "2_2") (pintype "passive"))
      (node (ref "C3") (pin "2") (pintype "passive"))
      (node (ref "C4") (pin "2") (pintype "passive"))
      (node (ref "C7") (pin "1") (pinfunction "1_1") (pintype "passive"))
      (node (ref "C8") (pin "2") (pinfunction "2_2") (pintype "passive"))
      (node (ref "R1") (pin "1") (pinfunction "1_1") (pintype "passive"))
      (node (ref "R10") (pin "2") (pinfunction "2_2") (pintype "passive"))
      (node (ref "R11") (pin "2") (pinfunction "2_2") (pintype "passive"))
      (node (ref "R12") (pin "2") (pinfunction "2_2") (pintype "passive"))
      (node (ref "R13") (pin "2") (pinfunction "2_2") (pintype "passive"))
      (node (ref "R14") (pin "2") (pinfunction "2_2") (pintype "passive"))
      (node (ref "R15") (pin "2") (pinfunction "2_2") (pintype "passive"))
      (node (ref "R16") (pin "2") (pinfunction "2_2") (pintype "passive"))
      (node (ref "R3") (pin "2") (pinfunction "2_2") (pintype "passive"))
      (node (ref "R5") (pin "2") (pinfunction "2_2") (pintype "passive"))
      (node (ref "R6") (pin "2") (pinfunction "2_2") (pintype "passive"))
      (node (ref "S1") (pin "1") (pinfunction "1_1") (pintype "passive"))
      (node (ref "U*1") (pin "10") (pinfunction "SCLR_10") (pintype "passive"))
      (node (ref "U*1") (pin "16") (pinfunction "VCC_16") (pintype "passive"))
      (node (ref "U*2") (pin "10") (pinfunction "SCLR_10") (pintype "passive"))
      (node (ref "U*2") (pin "16") (pinfunction "VCC_16") (pintype "passive"))
      (node (ref "U*3") (pin "10") (pinfunction "SCLR_10") (pintype "passive"))
      (node (ref "U*3") (pin "16") (pinfunction "VCC_16") (pintype "passive"))
      (node (ref "U*4") (pin "10") (pinfunction "SCLR_10") (pintype "passive"))
      (node (ref "U*4") (pin "16") (pinfunction "VCC_16") (pintype "passive"))
      (node (ref "U*5") (pin "10") (pinfunction "SCLR_10") (pintype "passive"))
      (node (ref "U*5") (pin "16") (pinfunction "VCC_16") (pintype "passive"))
      (node (ref "U2") (pin "2") (pinfunction "OUT1_2") (pintype "passive"))
      (node (ref "U2") (pin "4") (pinfunction "OUT2_4") (pintype "passive"))
      (node (ref "U3") (pin "9") (pinfunction "VCC_9") (pintype "passive"))
      (node (ref "U4") (pin "2") (pinfunction "VCC_2") (pintype "passive"))
      (node (ref "U5") (pin "1") (pinfunction "VBAT_1") (pintype "passive"))
      (node (ref "U5") (pin "24") (pinfunction "VDD_1_24") (pintype "passive"))
      (node (ref "U5") (pin "36") (pinfunction "VDD_2_36") (pintype "passive"))
      (node (ref "U5") (pin "48") (pinfunction "VDD_3_48") (pintype "passive"))
      (node (ref "U5") (pin "9") (pinfunction "VDDA_9") (pintype "passive"))
      (node (ref "U6") (pin "16") (pinfunction "VDD_16") (pintype "passive"))
    )
    (net (code "2") (name "/1") (class "Default")
      (node (ref "R28") (pin "2") (pinfunction "2_2") (pintype "passive"))
      (node (ref "U*1") (pin "15") (pinfunction "QA_15") (pintype "passive"))
    )
    (net (code "3") (name "/2") (class "Default")
      (node (ref "R29") (pin "2") (pinfunction "2_2") (pintype "passive"))
      (node (ref "U*1") (pin "1") (pinfunction "QB_1") (pintype "passive"))
    )
    (net (code "4") (name "/3") (class "Default")
      (node (ref "R30") (pin "2") (pinfunction "2_2") (pintype "passive"))
      (node (ref "U*1") (pin "2") (pinfunction "QC_2") (pintype "passive"))
    )
    (net (code "5") (name "/4") (class "Default")
      (node (ref "R40") (pin "2") (pinfunction "2_2") (pintype "passive"))
      (node (ref "U*1") (pin "3") (pinfunction "QD_3") (pintype "passive"))
    )
    (net (code "6") (name "/5") (class "Default")
      (node (ref "R39") (pin "2") (pinfunction "2_2") (pintype "passive"))
      (node (ref "U*1") (pin "4") (pinfunction "QE_4") (pintype "passive"))
    )
    (net (code "7") (name "/6") (class "Default")
      (node (ref "R38") (pin "2") (pinfunction "2_2") (pintype "passive"))
      (node (ref "U*1") (pin "5") (pinfunction "QF_5") (pintype "passive"))
    )
    (net (code "8") (name "/7") (class "Default")
      (node (ref "R37") (pin "2") (pinfunction "2_2") (pintype "passive"))
      (node (ref "U*1") (pin "6") (pinfunction "QG_6") (pintype "passive"))
    )
    (net (code "9") (name "/8") (class "Default")
      (node (ref "R47") (pin "2") (pinfunction "2_2") (pintype "passive"))
      (node (ref "U*1") (pin "7") (pinfunction "QH_7") (pintype "passive"))
    )
    (net (code "10") (name "/9") (class "Default")
      (node (ref "R48") (pin "2") (pinfunction "2_2") (pintype "passive"))
      (node (ref "U*2") (pin "15") (pinfunction "QA_15") (pintype "passive"))
    )
    (net (code "11") (name "/10") (class "Default")
      (node (ref "R27") (pin "2") (pinfunction "2_2") (pintype "passive"))
      (node (ref "U*2") (pin "1") (pinfunction "QB_1") (pintype "passive"))
    )
    (net (code "12") (name "/11") (class "Default")
      (node (ref "R32") (pin "2") (pinfunction "2_2") (pintype "passive"))
      (node (ref "U*2") (pin "2") (pinfunction "QC_2") (pintype "passive"))
    )
    (net (code "13") (name "/12") (class "Default")
      (node (ref "R33") (pin "2") (pinfunction "2_2") (pintype "passive"))
      (node (ref "U*2") (pin "3") (pinfunction "QD_3") (pintype "passive"))
    )
    (net (code "14") (name "/13") (class "Default")
      (node (ref "R34") (pin "2") (pinfunction "2_2") (pintype "passive"))
      (node (ref "U*2") (pin "4") (pinfunction "QE_4") (pintype "passive"))
    )
    (net (code "15") (name "/14") (class "Default")
      (node (ref "R44") (pin "2") (pinfunction "2_2") (pintype "passive"))
      (node (ref "U*2") (pin "5") (pinfunction "QF_5") (pintype "passive"))
    )
    (net (code "16") (name "/15") (class "Default")
      (node (ref "R43") (pin "2") (pinfunction "2_2") (pintype "passive"))
      (node (ref "U*2") (pin "6") (pinfunction "QG_6") (pintype "passive"))
    )
    (net (code "17") (name "/16") (class "Default")
      (node (ref "R42") (pin "2") (pinfunction "2_2") (pintype "passive"))
      (node (ref "U*2") (pin "7") (pinfunction "QH_7") (pintype "passive"))
    )
    (net (code "18") (name "/17") (class "Default")
      (node (ref "R41") (pin "2") (pinfunction "2_2") (pintype "passive"))
      (node (ref "U*3") (pin "15") (pinfunction "QA_15") (pintype "passive"))
    )
    (net (code "19") (name "/18") (class "Default")
      (node (ref "R49") (pin "2") (pinfunction "2_2") (pintype "passive"))
      (node (ref "U*3") (pin "1") (pinfunction "QB_1") (pintype "passive"))
    )
    (net (code "20") (name "/19") (class "Default")
      (node (ref "R50") (pin "2") (pinfunction "2_2") (pintype "passive"))
      (node (ref "U*3") (pin "2") (pinfunction "QC_2") (pintype "passive"))
    )
    (net (code "21") (name "/20") (class "Default")
      (node (ref "R31") (pin "2") (pinfunction "2_2") (pintype "passive"))
      (node (ref "U*3") (pin "3") (pinfunction "QD_3") (pintype "passive"))
    )
    (net (code "22") (name "/21") (class "Default")
      (node (ref "R52") (pin "2") (pinfunction "2_2") (pintype "passive"))
      (node (ref "U*3") (pin "4") (pinfunction "QE_4") (pintype "passive"))
    )
    (net (code "23") (name "/22") (class "Default")
      (node (ref "R53") (pin "2") (pinfunction "2_2") (pintype "passive"))
      (node (ref "U*3") (pin "5") (pinfunction "QF_5") (pintype "passive"))
    )
    (net (code "24") (name "/23") (class "Default")
      (node (ref "R54") (pin "2") (pinfunction "2_2") (pintype "passive"))
      (node (ref "U*3") (pin "6") (pinfunction "QG_6") (pintype "passive"))
    )
    (net (code "25") (name "/24") (class "Default")
      (node (ref "R64") (pin "2") (pinfunction "2_2") (pintype "passive"))
      (node (ref "U*3") (pin "7") (pinfunction "QH_7") (pintype "passive"))
    )
    (net (code "26") (name "/25") (class "Default")
      (node (ref "R63") (pin "2") (pinfunction "2_2") (pintype "passive"))
      (node (ref "U*4") (pin "15") (pinfunction "QA_15") (pintype "passive"))
    )
    (net (code "27") (name "/26") (class "Default")
      (node (ref "R62") (pin "2") (pinfunction "2_2") (pintype "passive"))
      (node (ref "U*4") (pin "1") (pinfunction "QB_1") (pintype "passive"))
    )
    (net (code "28") (name "/27") (class "Default")
      (node (ref "R61") (pin "2") (pinfunction "2_2") (pintype "passive"))
      (node (ref "U*4") (pin "2") (pinfunction "QC_2") (pintype "passive"))
    )
    (net (code "29") (name "/28") (class "Default")
      (node (ref "R71") (pin "2") (pinfunction "2_2") (pintype "passive"))
      (node (ref "U*4") (pin "3") (pinfunction "QD_3") (pintype "passive"))
    )
    (net (code "30") (name "/29") (class "Default")
      (node (ref "R72") (pin "2") (pinfunction "2_2") (pintype "passive"))
      (node (ref "U*4") (pin "4") (pinfunction "QE_4") (pintype "passive"))
    )
    (net (code "31") (name "/30") (class "Default")
      (node (ref "R51") (pin "2") (pinfunction "2_2") (pintype "passive"))
      (node (ref "U*4") (pin "5") (pinfunction "QF_5") (pintype "passive"))
    )
    (net (code "32") (name "/31") (class "Default")
      (node (ref "R56") (pin "2") (pinfunction "2_2") (pintype "passive"))
      (node (ref "U*4") (pin "6") (pinfunction "QG_6") (pintype "passive"))
    )
    (net (code "33") (name "/32") (class "Default")
      (node (ref "R57") (pin "2") (pinfunction "2_2") (pintype "passive"))
      (node (ref "U*4") (pin "7") (pinfunction "QH_7") (pintype "passive"))
    )
    (net (code "34") (name "/33") (class "Default")
      (node (ref "R58") (pin "2") (pinfunction "2_2") (pintype "passive"))
      (node (ref "U*5") (pin "15") (pinfunction "QA_15") (pintype "passive"))
    )
    (net (code "35") (name "/34") (class "Default")
      (node (ref "R68") (pin "2") (pinfunction "2_2") (pintype "passive"))
      (node (ref "U*5") (pin "1") (pinfunction "QB_1") (pintype "passive"))
    )
    (net (code "36") (name "/35") (class "Default")
      (node (ref "R67") (pin "2") (pinfunction "2_2") (pintype "passive"))
      (node (ref "U*5") (pin "2") (pinfunction "QC_2") (pintype "passive"))
    )
    (net (code "37") (name "/36") (class "Default")
      (node (ref "R66") (pin "2") (pinfunction "2_2") (pintype "passive"))
      (node (ref "U*5") (pin "3") (pinfunction "QD_3") (pintype "passive"))
    )
    (net (code "38") (name "/37") (class "Default")
      (node (ref "R65") (pin "2") (pinfunction "2_2") (pintype "passive"))
      (node (ref "U*5") (pin "4") (pinfunction "QE_4") (pintype "passive"))
    )
    (net (code "39") (name "/38") (class "Default")
      (node (ref "R73") (pin "2") (pinfunction "2_2") (pintype "passive"))
      (node (ref "U*5") (pin "5") (pinfunction "QF_5") (pintype "passive"))
    )
    (net (code "40") (name "/39") (class "Default")
      (node (ref "R74") (pin "2") (pinfunction "2_2") (pintype "passive"))
      (node (ref "U*5") (pin "6") (pinfunction "QG_6") (pintype "passive"))
    )
    (net (code "41") (name "/40") (class "Default")
      (node (ref "R55") (pin "2") (pinfunction "2_2") (pintype "passive"))
      (node (ref "U*5") (pin "7") (pinfunction "QH_7") (pintype "passive"))
    )
    (net (code "42") (name "/D1") (class "Default")
      (node (ref "R45") (pin "1") (pinfunction "1_1") (pintype "passive"))
      (node (ref "U5") (pin "33") (pinfunction "PA12/USART1_RTS/CANTX/USBDP/TIM1_ETR_33") (pintype "passive"))
    )
    (net (code "43") (name "/D2") (class "Default")
      (node (ref "U5") (pin "32") (pinfunction "PA11/USART1_CTS/CANRX/USBDM/TIM1_CH4_32") (pintype "passive"))
    )
    (net (code "44") (name "/DS_INT") (class "Default")
      (node (ref "R5") (pin "1") (pinfunction "1_1") (pintype "passive"))
      (node (ref "U4") (pin "3") (pinfunction "INT/SQW_3") (pintype "passive"))
      (node (ref "U5") (pin "41") (pinfunction "PB5/I2C1_SMBAI/TIM3_CH2/SPI1_MOSI_41") (pintype "passive"))
    )
    (net (code "45") (name "/DS_SCL") (class "Default")
      (node (ref "R3") (pin "1") (pinfunction "1_1") (pintype "passive"))
      (node (ref "U4") (pin "16") (pinfunction "SCL_16") (pintype "passive"))
      (node (ref "U5") (pin "45") (pinfunction "PB8/TIM4_CH3/I2C1_SCL/CANRX_45") (pintype "passive"))
    )
    (net (code "46") (name "/DS_SDA") (class "Default")
      (node (ref "R6") (pin "1") (pinfunction "1_1") (pintype "passive"))
      (node (ref "U4") (pin "15") (pinfunction "SDA_15") (pintype "passive"))
      (node (ref "U5") (pin "46") (pinfunction "PB9/TIM4_CH4/I2C1_SDA/CANTX_46") (pintype "passive"))
    )
    (net (code "47") (name "/EN") (class "Default")
      (node (ref "U*1") (pin "13") (pinfunction "OE_13") (pintype "passive"))
      (node (ref "U*2") (pin "13") (pinfunction "OE_13") (pintype "passive"))
      (node (ref "U*3") (pin "13") (pinfunction "OE_13") (pintype "passive"))
      (node (ref "U*4") (pin "13") (pinfunction "OE_13") (pintype "passive"))
      (node (ref "U*5") (pin "13") (pinfunction "OE_13") (pintype "passive"))
      (node (ref "U5") (pin "18") (pinfunction "PB0/ADC12_IN8/TIM3_CH3/TIM1_CH2N_18") (pintype "passive"))
    )
    (net (code "48") (name "/Key2") (class "Default")
      (node (ref "R15") (pin "1") (pinfunction "1_1") (pintype "passive"))
      (node (ref "U6") (pin "11") (pinfunction "OUT4_11") (pintype "passive"))
    )
    (net (code "49") (name "/Key3") (class "Default")
      (node (ref "R16") (pin "1") (pinfunction "1_1") (pintype "passive"))
      (node (ref "U6") (pin "10") (pinfunction "OUT5_10") (pintype "passive"))
    )
    (net (code "50") (name "/LED_RGB") (class "Default")
      (node (ref "L1") (pin "4") (pinfunction "DIN_4") (pintype "passive"))
      (node (ref "U5") (pin "38") (pinfunction "PA15/JTDI/TIM2_CH1_ETR/SPI1_NSS_38") (pintype "passive"))
    )
    (net (code "51") (name "/N1_0") (class "Default")
      (node (ref "N1") (pin "3") (pinfunction "0_3") (pintype "passive"))
      (node (ref "Q2") (pin "2") (pinfunction "B_2") (pintype "passive"))
    )
    (net (code "52") (name "/N1_1") (class "Default")
      (node (ref "N1") (pin "12") (pinfunction "1_12") (pintype "passive"))
      (node (ref "Q3") (pin "2") (pinfunction "B_2") (pintype "passive"))
    )
    (net (code "53") (name "/N1_2") (class "Default")
      (node (ref "N1") (pin "11") (pinfunction "2_11") (pintype "passive"))
      (node (ref "Q4") (pin "2") (pinfunction "B_2") (pintype "passive"))
    )
    (net (code "54") (name "/N1_3") (class "Default")
      (node (ref "N1") (pin "10") (pinfunction "3_10") (pintype "passive"))
      (node (ref "Q5") (pin "2") (pinfunction "B_2") (pintype "passive"))
    )
    (net (code "55") (name "/N1_4") (class "Default")
      (node (ref "N1") (pin "9") (pinfunction "4_9") (pintype "passive"))
      (node (ref "Q13") (pin "2") (pinfunction "B_2") (pintype "passive"))
    )
    (net (code "56") (name "/N1_5") (class "Default")
      (node (ref "N1") (pin "8") (pinfunction "5_8") (pintype "passive"))
      (node (ref "Q12") (pin "2") (pinfunction "B_2") (pintype "passive"))
    )
    (net (code "57") (name "/N1_6") (class "Default")
      (node (ref "N1") (pin "7") (pinfunction "6_7") (pintype "passive"))
      (node (ref "Q11") (pin "2") (pinfunction "B_2") (pintype "passive"))
    )
    (net (code "58") (name "/N1_7") (class "Default")
      (node (ref "N1") (pin "6") (pinfunction "7_6") (pintype "passive"))
      (node (ref "Q10") (pin "2") (pinfunction "B_2") (pintype "passive"))
    )
    (net (code "59") (name "/N1_8") (class "Default")
      (node (ref "N1") (pin "5") (pinfunction "8_5") (pintype "passive"))
      (node (ref "Q20") (pin "2") (pinfunction "B_2") (pintype "passive"))
    )
    (net (code "60") (name "/N1_9") (class "Default")
      (node (ref "N1") (pin "4") (pinfunction "9_4") (pintype "passive"))
      (node (ref "Q21") (pin "2") (pinfunction "B_2") (pintype "passive"))
    )
    (net (code "61") (name "/N2_0") (class "Default")
      (node (ref "N3") (pin "3") (pinfunction "0_3") (pintype "passive"))
      (node (ref "Q6") (pin "2") (pinfunction "B_2") (pintype "passive"))
    )
    (net (code "62") (name "/N2_1") (class "Default")
      (node (ref "N3") (pin "12") (pinfunction "1_12") (pintype "passive"))
      (node (ref "Q7") (pin "2") (pinfunction "B_2") (pintype "passive"))
    )
    (net (code "63") (name "/N2_2") (class "Default")
      (node (ref "N3") (pin "11") (pinfunction "2_11") (pintype "passive"))
      (node (ref "Q8") (pin "2") (pinfunction "B_2") (pintype "passive"))
    )
    (net (code "64") (name "/N2_3") (class "Default")
      (node (ref "N3") (pin "10") (pinfunction "3_10") (pintype "passive"))
      (node (ref "Q9") (pin "2") (pinfunction "B_2") (pintype "passive"))
    )
    (net (code "65") (name "/N2_4") (class "Default")
      (node (ref "N3") (pin "9") (pinfunction "4_9") (pintype "passive"))
      (node (ref "Q17") (pin "2") (pinfunction "B_2") (pintype "passive"))
    )
    (net (code "66") (name "/N2_5") (class "Default")
      (node (ref "N3") (pin "8") (pinfunction "5_8") (pintype "passive"))
      (node (ref "Q16") (pin "2") (pinfunction "B_2") (pintype "passive"))
    )
    (net (code "67") (name "/N2_6") (class "Default")
      (node (ref "N3") (pin "7") (pinfunction "6_7") (pintype "passive"))
      (node (ref "Q15") (pin "2") (pinfunction "B_2") (pintype "passive"))
    )
    (net (code "68") (name "/N2_7") (class "Default")
      (node (ref "N3") (pin "6") (pinfunction "7_6") (pintype "passive"))
      (node (ref "Q14") (pin "2") (pinfunction "B_2") (pintype "passive"))
    )
    (net (code "69") (name "/N2_8") (class "Default")
      (node (ref "N3") (pin "5") (pinfunction "8_5") (pintype "passive"))
      (node (ref "Q22") (pin "2") (pinfunction "B_2") (pintype "passive"))
    )
    (net (code "70") (name "/N2_9") (class "Default")
      (node (ref "N3") (pin "4") (pinfunction "9_4") (pintype "passive"))
      (node (ref "Q23") (pin "2") (pinfunction "B_2") (pintype "passive"))
    )
    (net (code "71") (name "/N3_0") (class "Default")
      (node (ref "N2") (pin "3") (pinfunction "0_3") (pintype "passive"))
      (node (ref "Q24") (pin "2") (pinfunction "B_2") (pintype "passive"))
    )
    (net (code "72") (name "/N3_1") (class "Default")
      (node (ref "N2") (pin "12") (pinfunction "1_12") (pintype "passive"))
      (node (ref "Q25") (pin "2") (pinfunction "B_2") (pintype "passive"))
    )
    (net (code "73") (name "/N3_2") (class "Default")
      (node (ref "N2") (pin "11") (pinfunction "2_11") (pintype "passive"))
      (node (ref "Q26") (pin "2") (pinfunction "B_2") (pintype "passive"))
    )
    (net (code "74") (name "/N3_3") (class "Default")
      (node (ref "N2") (pin "10") (pinfunction "3_10") (pintype "passive"))
      (node (ref "Q27") (pin "2") (pinfunction "B_2") (pintype "passive"))
    )
    (net (code "75") (name "/N3_4") (class "Default")
      (node (ref "N2") (pin "9") (pinfunction "4_9") (pintype "passive"))
      (node (ref "Q35") (pin "2") (pinfunction "B_2") (pintype "passive"))
    )
    (net (code "76") (name "/N3_5") (class "Default")
      (node (ref "N2") (pin "8") (pinfunction "5_8") (pintype "passive"))
      (node (ref "Q34") (pin "2") (pinfunction "B_2") (pintype "passive"))
    )
    (net (code "77") (name "/N3_6") (class "Default")
      (node (ref "N2") (pin "7") (pinfunction "6_7") (pintype "passive"))
      (node (ref "Q33") (pin "2") (pinfunction "B_2") (pintype "passive"))
    )
    (net (code "78") (name "/N3_7") (class "Default")
      (node (ref "N2") (pin "6") (pinfunction "7_6") (pintype "passive"))
      (node (ref "Q32") (pin "2") (pinfunction "B_2") (pintype "passive"))
    )
    (net (code "79") (name "/N3_8") (class "Default")
      (node (ref "N2") (pin "5") (pinfunction "8_5") (pintype "passive"))
      (node (ref "Q40") (pin "2") (pinfunction "B_2") (pintype "passive"))
    )
    (net (code "80") (name "/N3_9") (class "Default")
      (node (ref "N2") (pin "4") (pinfunction "9_4") (pintype "passive"))
      (node (ref "Q41") (pin "2") (pinfunction "B_2") (pintype "passive"))
    )
    (net (code "81") (name "/N4_0") (class "Default")
      (node (ref "N4") (pin "3") (pinfunction "0_3") (pintype "passive"))
      (node (ref "Q28") (pin "2") (pinfunction "B_2") (pintype "passive"))
    )
    (net (code "82") (name "/N4_1") (class "Default")
      (node (ref "N4") (pin "12") (pinfunction "1_12") (pintype "passive"))
      (node (ref "Q29") (pin "2") (pinfunction "B_2") (pintype "passive"))
    )
    (net (code "83") (name "/N4_2") (class "Default")
      (node (ref "N4") (pin "11") (pinfunction "2_11") (pintype "passive"))
      (node (ref "Q30") (pin "2") (pinfunction "B_2") (pintype "passive"))
    )
    (net (code "84") (name "/N4_3") (class "Default")
      (node (ref "N4") (pin "10") (pinfunction "3_10") (pintype "passive"))
      (node (ref "Q31") (pin "2") (pinfunction "B_2") (pintype "passive"))
    )
    (net (code "85") (name "/N4_4") (class "Default")
      (node (ref "N4") (pin "9") (pinfunction "4_9") (pintype "passive"))
      (node (ref "Q39") (pin "2") (pinfunction "B_2") (pintype "passive"))
    )
    (net (code "86") (name "/N4_5") (class "Default")
      (node (ref "N4") (pin "8") (pinfunction "5_8") (pintype "passive"))
      (node (ref "Q38") (pin "2") (pinfunction "B_2") (pintype "passive"))
    )
    (net (code "87") (name "/N4_6") (class "Default")
      (node (ref "N4") (pin "7") (pinfunction "6_7") (pintype "passive"))
      (node (ref "Q37") (pin "2") (pinfunction "B_2") (pintype "passive"))
    )
    (net (code "88") (name "/N4_7") (class "Default")
      (node (ref "N4") (pin "6") (pinfunction "7_6") (pintype "passive"))
      (node (ref "Q36") (pin "2") (pinfunction "B_2") (pintype "passive"))
    )
    (net (code "89") (name "/N4_8") (class "Default")
      (node (ref "N4") (pin "5") (pinfunction "8_5") (pintype "passive"))
      (node (ref "Q42") (pin "2") (pinfunction "B_2") (pintype "passive"))
    )
    (net (code "90") (name "/N4_9") (class "Default")
      (node (ref "N4") (pin "4") (pinfunction "9_4") (pintype "passive"))
      (node (ref "Q43") (pin "2") (pinfunction "B_2") (pintype "passive"))
    )
    (net (code "91") (name "/OSC_IN") (class "Default")
      (node (ref "C6") (pin "1") (pinfunction "1_1") (pintype "passive"))
      (node (ref "U5") (pin "5") (pinfunction "PD0/OSC_IN_5") (pintype "passive"))
      (node (ref "Y1") (pin "1") (pinfunction "1_1") (pintype "passive"))
    )
    (net (code "92") (name "/OSC_OUT") (class "Default")
      (node (ref "C5") (pin "1") (pinfunction "1_1") (pintype "passive"))
      (node (ref "U5") (pin "6") (pinfunction "PDI/OSC_OUT_6") (pintype "passive"))
      (node (ref "Y1") (pin "2") (pinfunction "2_2") (pintype "passive"))
    )
    (net (code "93") (name "/PA10") (class "Default")
      (node (ref "U5") (pin "31") (pinfunction "PA10/USART1_RX/TIM1_CH3_31") (pintype "passive"))
    )
    (net (code "94") (name "/PB4") (class "Default")
      (node (ref "R7") (pin "2") (pinfunction "2_2") (pintype "passive"))
      (node (ref "U5") (pin "40") (pinfunction "PB4/JNTRST/TIM3_CH1/SPI1_MISO_40") (pintype "passive"))
    )
    (net (code "95") (name "/PB12") (class "Default")
      (node (ref "R11") (pin "1") (pinfunction "1_1") (pintype "passive"))
      (node (ref "U5") (pin "25") (pinfunction "PB12/SPI2_NSS/I2C2_SMBAI/USART3_CK/TIM1_BKIN_25") (pintype "passive"))
      (node (ref "U6") (pin "15") (pinfunction "OUT0_15") (pintype "passive"))
    )
    (net (code "96") (name "/PB13") (class "Default")
      (node (ref "R12") (pin "1") (pinfunction "1_1") (pintype "passive"))
      (node (ref "U5") (pin "26") (pinfunction "PB13/SPI2_SCK/USART3_CTS/TIM1_CH1N_26") (pintype "passive"))
      (node (ref "U6") (pin "14") (pinfunction "OUT1_14") (pintype "passive"))
    )
    (net (code "97") (name "/PB14") (class "Default")
      (node (ref "R13") (pin "1") (pinfunction "1_1") (pintype "passive"))
      (node (ref "U5") (pin "27") (pinfunction "PB14/SPI2_MISO/USART3_RTS/TIM1_CH2N_27") (pintype "passive"))
      (node (ref "U6") (pin "13") (pinfunction "OUT2_13") (pintype "passive"))
    )
    (net (code "98") (name "/PB15") (class "Default")
      (node (ref "R14") (pin "1") (pinfunction "1_1") (pintype "passive"))
      (node (ref "U5") (pin "28") (pinfunction "PB15/SPI2_MOSI/TIM1_CH3N_28") (pintype "passive"))
      (node (ref "U6") (pin "12") (pinfunction "OUT3_12") (pintype "passive"))
    )
    (net (code "99") (name "/RCK") (class "Default")
      (node (ref "U*1") (pin "12") (pinfunction "RCLK_12") (pintype "passive"))
      (node (ref "U*2") (pin "12") (pinfunction "RCLK_12") (pintype "passive"))
      (node (ref "U*3") (pin "12") (pinfunction "RCLK_12") (pintype "passive"))
      (node (ref "U*4") (pin "12") (pinfunction "RCLK_12") (pintype "passive"))
      (node (ref "U*5") (pin "12") (pinfunction "RCLK_12") (pintype "passive"))
      (node (ref "U5") (pin "14") (pinfunction "PA4/SPI1_NSS/USART2_CK/ADC12_IN4_14") (pintype "passive"))
    )
    (net (code "100") (name "/SCK") (class "Default")
      (node (ref "U*1") (pin "11") (pinfunction "SCK_11") (pintype "passive"))
      (node (ref "U*2") (pin "11") (pinfunction "SCK_11") (pintype "passive"))
      (node (ref "U*3") (pin "11") (pinfunction "SCK_11") (pintype "passive"))
      (node (ref "U*4") (pin "11") (pinfunction "SCK_11") (pintype "passive"))
      (node (ref "U*5") (pin "11") (pinfunction "SCK_11") (pintype "passive"))
      (node (ref "U5") (pin "15") (pinfunction "PA5/SPI1_SCK/ADC12_IN5_15") (pintype "passive"))
    )
    (net (code "101") (name "/SI") (class "Default")
      (node (ref "U*1") (pin "14") (pinfunction "SI_14") (pintype "passive"))
      (node (ref "U5") (pin "17") (pinfunction "PA7/SPI1_MOSI/ADC12_IN7/TIM3_CH2/TIM1_CH1N_17") (pintype "passive"))
    )
    (net (code "102") (name "/SWCLK(PA14)") (class "Default")
      (node (ref "S1") (pin "4") (pinfunction "4_4") (pintype "passive"))
      (node (ref "U5") (pin "37") (pinfunction "PA14/JTCK/SWCLK_37") (pintype "passive"))
    )
    (net (code "103") (name "/SWDIO(PA13)") (class "Default")
      (node (ref "S1") (pin "3") (pinfunction "3_3") (pintype "passive"))
      (node (ref "U5") (pin "34") (pinfunction "PA13/JTMS/SWDIO_34") (pintype "passive"))
    )
    (net (code "104") (name "/USART1-RX") (class "Default")
      (node (ref "U3") (pin "2") (pinfunction "UART_TX_2") (pintype "passive"))
      (node (ref "U5") (pin "43") (pinfunction "PB7/I2C1_SDA/TIM4_CH2/USART1_RX_43") (pintype "passive"))
    )
    (net (code "105") (name "/USART1-TX") (class "Default")
      (node (ref "U3") (pin "4") (pinfunction "UART_RX_4") (pintype "passive"))
      (node (ref "U5") (pin "42") (pinfunction "PB6/I2C1_SCL/TIM4_CH1/USART1_TX_42") (pintype "passive"))
    )
    (net (code "106") (name "5V") (class "Default")
      (node (ref "5") (pin "2") (pinfunction "2_2") (pintype "passive"))
      (node (ref "6") (pin "2") (pinfunction "2_2") (pintype "passive"))
      (node (ref "7") (pin "2") (pinfunction "2_2") (pintype "passive"))
      (node (ref "8") (pin "2") (pinfunction "2_2") (pintype "passive"))
      (node (ref "C1") (pin "2") (pintype "passive"))
      (node (ref "C2") (pin "2") (pintype "passive"))
      (node (ref "LS1") (pin "1") (pinfunction "1_1") (pintype "passive"))
      (node (ref "P1") (pin "1") (pinfunction "1_1") (pintype "passive"))
      (node (ref "P2") (pin "2") (pinfunction "2_2") (pintype "passive"))
      (node (ref "R17") (pin "1") (pinfunction "1_1") (pintype "passive"))
      (node (ref "R18") (pin "1") (pinfunction "1_1") (pintype "passive"))
      (node (ref "R26") (pin "1") (pinfunction "1_1") (pintype "passive"))
      (node (ref "R9") (pin "1") (pinfunction "1_1") (pintype "passive"))
      (node (ref "U1") (pin "1") (pinfunction "1_1") (pintype "passive"))
      (node (ref "U2") (pin "3") (pinfunction "IN_3") (pintype "passive"))
    )
    (net (code "107") (name "GND") (class "Default")
      (node (ref "1") (pin "1") (pinfunction "1_1") (pintype "passive"))
      (node (ref "2") (pin "1") (pinfunction "1_1") (pintype "passive"))
      (node (ref "3") (pin "1") (pinfunction "1_1") (pintype "passive"))
      (node (ref "4") (pin "1") (pinfunction "1_1") (pintype "passive"))
      (node (ref "5") (pin "1") (pinfunction "1_1") (pintype "passive"))
      (node (ref "6") (pin "1") (pinfunction "1_1") (pintype "passive"))
      (node (ref "7") (pin "1") (pinfunction "1_1") (pintype "passive"))
      (node (ref "8") (pin "1") (pinfunction "1_1") (pintype "passive"))
      (node (ref "9") (pin "2") (pinfunction "2_2") (pintype "passive"))
      (node (ref "BAT1") (pin "2") (pinfunction "2_2") (pintype "passive"))
      (node (ref "C1") (pin "1") (pintype "passive"))
      (node (ref "C10") (pin "1") (pinfunction "1_1") (pintype "passive"))
      (node (ref "C2") (pin "1") (pintype "passive"))
      (node (ref "C3") (pin "1") (pintype "passive"))
      (node (ref "C4") (pin "1") (pintype "passive"))
      (node (ref "C5") (pin "2") (pinfunction "2_2") (pintype "passive"))
      (node (ref "C6") (pin "2") (pinfunction "2_2") (pintype "passive"))
      (node (ref "C7") (pin "2") (pinfunction "2_2") (pintype "passive"))
      (node (ref "C8") (pin "1") (pinfunction "1_1") (pintype "passive"))
      (node (ref "C9") (pin "1") (pinfunction "1_1") (pintype "passive"))
      (node (ref "L1") (pin "3") (pinfunction "GND_3") (pintype "passive"))
      (node (ref "L2") (pin "3") (pinfunction "GND_3") (pintype "passive"))
      (node (ref "L3") (pin "3") (pinfunction "GND_3") (pintype "passive"))
      (node (ref "L4") (pin "3") (pinfunction "GND_3") (pintype "passive"))
      (node (ref "LED1") (pin "2") (pinfunction "K_2") (pintype "passive"))
      (node (ref "P1") (pin "2") (pinfunction "2_2") (pintype "passive"))
      (node (ref "P1") (pin "3") (pinfunction "3_3") (pintype "passive"))
      (node (ref "P2") (pin "1") (pinfunction "1_1") (pintype "passive"))
      (node (ref "Q1") (pin "3") (pinfunction "C_3") (pintype "passive"))
      (node (ref "Q10") (pin "3") (pinfunction "C_3") (pintype "passive"))
      (node (ref "Q11") (pin "3") (pinfunction "C_3") (pintype "passive"))
      (node (ref "Q12") (pin "3") (pinfunction "C_3") (pintype "passive"))
      (node (ref "Q13") (pin "3") (pinfunction "C_3") (pintype "passive"))
      (node (ref "Q14") (pin "3") (pinfunction "C_3") (pintype "passive"))
      (node (ref "Q15") (pin "3") (pinfunction "C_3") (pintype "passive"))
      (node (ref "Q16") (pin "3") (pinfunction "C_3") (pintype "passive"))
      (node (ref "Q17") (pin "3") (pinfunction "C_3") (pintype "passive"))
      (node (ref "Q18") (pin "3") (pinfunction "C_3") (pintype "passive"))
      (node (ref "Q2") (pin "3") (pinfunction "C_3") (pintype "passive"))
      (node (ref "Q20") (pin "3") (pinfunction "C_3") (pintype "passive"))
      (node (ref "Q21") (pin "3") (pinfunction "C_3") (pintype "passive"))
      (node (ref "Q22") (pin "3") (pinfunction "C_3") (pintype "passive"))
      (node (ref "Q23") (pin "3") (pinfunction "C_3") (pintype "passive"))
      (node (ref "Q24") (pin "3") (pinfunction "C_3") (pintype "passive"))
      (node (ref "Q25") (pin "3") (pinfunction "C_3") (pintype "passive"))
      (node (ref "Q26") (pin "3") (pinfunction "C_3") (pintype "passive"))
      (node (ref "Q27") (pin "3") (pinfunction "C_3") (pintype "passive"))
      (node (ref "Q28") (pin "3") (pinfunction "C_3") (pintype "passive"))
      (node (ref "Q29") (pin "3") (pinfunction "C_3") (pintype "passive"))
      (node (ref "Q3") (pin "3") (pinfunction "C_3") (pintype "passive"))
      (node (ref "Q30") (pin "3") (pinfunction "C_3") (pintype "passive"))
      (node (ref "Q31") (pin "3") (pinfunction "C_3") (pintype "passive"))
      (node (ref "Q32") (pin "3") (pinfunction "C_3") (pintype "passive"))
      (node (ref "Q33") (pin "3") (pinfunction "C_3") (pintype "passive"))
      (node (ref "Q34") (pin "3") (pinfunction "C_3") (pintype "passive"))
      (node (ref "Q35") (pin "3") (pinfunction "C_3") (pintype "passive"))
      (node (ref "Q36") (pin "3") (pinfunction "C_3") (pintype "passive"))
      (node (ref "Q37") (pin "3") (pinfunction "C_3") (pintype "passive"))
      (node (ref "Q38") (pin "3") (pinfunction "C_3") (pintype "passive"))
      (node (ref "Q39") (pin "3") (pinfunction "C_3") (pintype "passive"))
      (node (ref "Q4") (pin "3") (pinfunction "C_3") (pintype "passive"))
      (node (ref "Q40") (pin "3") (pinfunction "C_3") (pintype "passive"))
      (node (ref "Q41") (pin "3") (pinfunction "C_3") (pintype "passive"))
      (node (ref "Q42") (pin "3") (pinfunction "C_3") (pintype "passive"))
      (node (ref "Q43") (pin "3") (pinfunction "C_3") (pintype "passive"))
      (node (ref "Q5") (pin "3") (pinfunction "C_3") (pintype "passive"))
      (node (ref "Q6") (pin "3") (pinfunction "C_3") (pintype "passive"))
      (node (ref "Q7") (pin "3") (pinfunction "C_3") (pintype "passive"))
      (node (ref "Q8") (pin "3") (pinfunction "C_3") (pintype "passive"))
      (node (ref "Q9") (pin "3") (pinfunction "C_3") (pintype "passive"))
      (node (ref "R2") (pin "1") (pinfunction "1_1") (pintype "passive"))
      (node (ref "R2") (pin "2") (pinfunction "2_2") (pintype "passive"))
      (node (ref "R25") (pin "2") (pinfunction "2_2") (pintype "passive"))
      (node (ref "R4") (pin "1") (pinfunction "1_1") (pintype "passive"))
      (node (ref "R4") (pin "2") (pinfunction "2_2") (pintype "passive"))
      (node (ref "R8") (pin "1") (pinfunction "1_1") (pintype "passive"))
      (node (ref "S1") (pin "2") (pinfunction "2_2") (pintype "passive"))
      (node (ref "U*1") (pin "8") (pinfunction "GND_8") (pintype "passive"))
      (node (ref "U*2") (pin "8") (pinfunction "GND_8") (pintype "passive"))
      (node (ref "U*3") (pin "8") (pinfunction "GND_8") (pintype "passive"))
      (node (ref "U*4") (pin "8") (pinfunction "GND_8") (pintype "passive"))
      (node (ref "U*5") (pin "8") (pinfunction "GND_8") (pintype "passive"))
      (node (ref "U1") (pin "4") (pinfunction "4_4") (pintype "passive"))
      (node (ref "U1") (pin "5") (pinfunction "5_5") (pintype "passive"))
      (node (ref "U2") (pin "1") (pinfunction "GND_1") (pintype "passive"))
      (node (ref "U3") (pin "12") (pinfunction "GND_12") (pintype "passive"))
      (node (ref "U4") (pin "10") (pinfunction "N.C._10") (pintype "passive"))
      (node (ref "U4") (pin "11") (pinfunction "N.C._11") (pintype "passive"))
      (node (ref "U4") (pin "12") (pinfunction "N.C._12") (pintype "passive"))
      (node (ref "U4") (pin "13") (pinfunction "GND_13") (pintype "passive"))
      (node (ref "U4") (pin "5") (pinfunction "N.C._5") (pintype "passive"))
      (node (ref "U4") (pin "6") (pinfunction "N.C._6") (pintype "passive"))
      (node (ref "U4") (pin "7") (pinfunction "N.C._7") (pintype "passive"))
      (node (ref "U4") (pin "8") (pinfunction "N.C._8") (pintype "passive"))
      (node (ref "U4") (pin "9") (pinfunction "N.C._9") (pintype "passive"))
      (node (ref "U5") (pin "23") (pinfunction "VSS_1_23") (pintype "passive"))
      (node (ref "U5") (pin "35") (pinfunction "VSS_2_35") (pintype "passive"))
      (node (ref "U5") (pin "47") (pinfunction "VSS_3_47") (pintype "passive"))
      (node (ref "U5") (pin "8") (pinfunction "VSSA_8") (pintype "passive"))
      (node (ref "U6") (pin "1") (pinfunction "GND_1") (pintype "passive"))
    )
    (net (code "108") (name "Net-(D1-A)") (class "Default")
      (node (ref "D1") (pin "1") (pinfunction "A_1") (pintype "passive"))
      (node (ref "R35") (pin "2") (pinfunction "2_2") (pintype "passive"))
    )
    (net (code "109") (name "Net-(D1-K)") (class "Default")
      (node (ref "D1") (pin "2") (pinfunction "K_2") (pintype "passive"))
      (node (ref "D2") (pin "2") (pinfunction "K_2") (pintype "passive"))
      (node (ref "Q18") (pin "2") (pinfunction "B_2") (pintype "passive"))
    )
    (net (code "110") (name "Net-(D2-A)") (class "Default")
      (node (ref "D2") (pin "1") (pinfunction "A_1") (pintype "passive"))
      (node (ref "R36") (pin "2") (pinfunction "2_2") (pintype "passive"))
    )
    (net (code "111") (name "Net-(L1-DOUT)") (class "Default")
      (node (ref "L1") (pin "2") (pinfunction "DOUT_2") (pintype "passive"))
      (node (ref "L2") (pin "4") (pinfunction "DIN_4") (pintype "passive"))
    )
    (net (code "112") (name "Net-(L1-VDD)") (class "Default")
      (node (ref "L1") (pin "1") (pinfunction "VDD_1") (pintype "passive"))
      (node (ref "R9") (pin "2") (pinfunction "2_2") (pintype "passive"))
    )
    (net (code "113") (name "Net-(L2-DOUT)") (class "Default")
      (node (ref "L2") (pin "2") (pinfunction "DOUT_2") (pintype "passive"))
      (node (ref "L3") (pin "4") (pinfunction "DIN_4") (pintype "passive"))
    )
    (net (code "114") (name "Net-(L2-VDD)") (class "Default")
      (node (ref "L2") (pin "1") (pinfunction "VDD_1") (pintype "passive"))
      (node (ref "R17") (pin "2") (pinfunction "2_2") (pintype "passive"))
    )
    (net (code "115") (name "Net-(L3-DOUT)") (class "Default")
      (node (ref "L3") (pin "2") (pinfunction "DOUT_2") (pintype "passive"))
      (node (ref "L4") (pin "4") (pinfunction "DIN_4") (pintype "passive"))
    )
    (net (code "116") (name "Net-(L3-VDD)") (class "Default")
      (node (ref "L3") (pin "1") (pinfunction "VDD_1") (pintype "passive"))
      (node (ref "R18") (pin "2") (pinfunction "2_2") (pintype "passive"))
    )
    (net (code "117") (name "Net-(L4-VDD)") (class "Default")
      (node (ref "L4") (pin "1") (pinfunction "VDD_1") (pintype "passive"))
      (node (ref "R26") (pin "2") (pinfunction "2_2") (pintype "passive"))
    )
    (net (code "118") (name "Net-(LED1-A)") (class "Default")
      (node (ref "LED1") (pin "1") (pinfunction "A_1") (pintype "passive"))
      (node (ref "R1") (pin "2") (pinfunction "2_2") (pintype "passive"))
    )
    (net (code "119") (name "Net-(N1-VCC)") (class "Default")
      (node (ref "N1") (pin "1") (pinfunction "VCC_1") (pintype "passive"))
      (node (ref "R59") (pin "1") (pinfunction "1_1") (pintype "passive"))
    )
    (net (code "120") (name "Net-(N2-VCC)") (class "Default")
      (node (ref "N2") (pin "1") (pinfunction "VCC_1") (pintype "passive"))
      (node (ref "R60") (pin "1") (pinfunction "1_1") (pintype "passive"))
    )
    (net (code "121") (name "Net-(N3-VCC)") (class "Default")
      (node (ref "N3") (pin "1") (pinfunction "VCC_1") (pintype "passive"))
      (node (ref "R69") (pin "1") (pinfunction "1_1") (pintype "passive"))
    )
    (net (code "122") (name "Net-(N4-VCC)") (class "Default")
      (node (ref "N4") (pin "1") (pinfunction "VCC_1") (pintype "passive"))
      (node (ref "R70") (pin "1") (pinfunction "1_1") (pintype "passive"))
    )
    (net (code "123") (name "Net-(PAD1-Pad1)") (class "Default")
      (node (ref "PAD1") (pin "1") (pinfunction "1_1") (pintype "passive"))
      (node (ref "R19") (pin "1") (pinfunction "1_1") (pintype "passive"))
    )
    (net (code "124") (name "Net-(PAD2-Pad1)") (class "Default")
      (node (ref "PAD2") (pin "1") (pinfunction "1_1") (pintype "passive"))
      (node (ref "R20") (pin "1") (pinfunction "1_1") (pintype "passive"))
    )
    (net (code "125") (name "Net-(PAD3-Pad1)") (class "Default")
      (node (ref "PAD3") (pin "1") (pinfunction "1_1") (pintype "passive"))
      (node (ref "R21") (pin "1") (pinfunction "1_1") (pintype "passive"))
    )
    (net (code "126") (name "Net-(PAD4-Pad1)") (class "Default")
      (node (ref "PAD4") (pin "1") (pinfunction "1_1") (pintype "passive"))
      (node (ref "R22") (pin "1") (pinfunction "1_1") (pintype "passive"))
    )
    (net (code "127") (name "Net-(PAD5-Pad1)") (class "Default")
      (node (ref "PAD5") (pin "1") (pinfunction "1_1") (pintype "passive"))
      (node (ref "R23") (pin "1") (pinfunction "1_1") (pintype "passive"))
    )
    (net (code "128") (name "Net-(PAD6-Pad1)") (class "Default")
      (node (ref "PAD6") (pin "1") (pinfunction "1_1") (pintype "passive"))
      (node (ref "R24") (pin "1") (pinfunction "1_1") (pintype "passive"))
    )
    (net (code "129") (name "Net-(Q1-B)") (class "Default")
      (node (ref "LS1") (pin "2") (pinfunction "2_2") (pintype "passive"))
      (node (ref "Q1") (pin "2") (pinfunction "B_2") (pintype "passive"))
    )
    (net (code "130") (name "Net-(Q1-E)") (class "Default")
      (node (ref "Q1") (pin "1") (pinfunction "E_1") (pintype "passive"))
      (node (ref "R7") (pin "1") (pinfunction "1_1") (pintype "passive"))
    )
    (net (code "131") (name "Net-(Q2-E)") (class "Default")
      (node (ref "Q2") (pin "1") (pinfunction "E_1") (pintype "passive"))
      (node (ref "R27") (pin "1") (pinfunction "1_1") (pintype "passive"))
    )
    (net (code "132") (name "Net-(Q3-E)") (class "Default")
      (node (ref "Q3") (pin "1") (pinfunction "E_1") (pintype "passive"))
      (node (ref "R28") (pin "1") (pinfunction "1_1") (pintype "passive"))
    )
    (net (code "133") (name "Net-(Q4-E)") (class "Default")
      (node (ref "Q4") (pin "1") (pinfunction "E_1") (pintype "passive"))
      (node (ref "R29") (pin "1") (pinfunction "1_1") (pintype "passive"))
    )
    (net (code "134") (name "Net-(Q5-E)") (class "Default")
      (node (ref "Q5") (pin "1") (pinfunction "E_1") (pintype "passive"))
      (node (ref "R30") (pin "1") (pinfunction "1_1") (pintype "passive"))
    )
    (net (code "135") (name "Net-(Q6-E)") (class "Default")
      (node (ref "Q6") (pin "1") (pinfunction "E_1") (pintype "passive"))
      (node (ref "R31") (pin "1") (pinfunction "1_1") (pintype "passive"))
    )
    (net (code "136") (name "Net-(Q7-E)") (class "Default")
      (node (ref "Q7") (pin "1") (pinfunction "E_1") (pintype "passive"))
      (node (ref "R32") (pin "1") (pinfunction "1_1") (pintype "passive"))
    )
    (net (code "137") (name "Net-(Q8-E)") (class "Default")
      (node (ref "Q8") (pin "1") (pinfunction "E_1") (pintype "passive"))
      (node (ref "R33") (pin "1") (pinfunction "1_1") (pintype "passive"))
    )
    (net (code "138") (name "Net-(Q9-E)") (class "Default")
      (node (ref "Q9") (pin "1") (pinfunction "E_1") (pintype "passive"))
      (node (ref "R34") (pin "1") (pinfunction "1_1") (pintype "passive"))
    )
    (net (code "139") (name "Net-(Q10-E)") (class "Default")
      (node (ref "Q10") (pin "1") (pinfunction "E_1") (pintype "passive"))
      (node (ref "R37") (pin "1") (pinfunction "1_1") (pintype "passive"))
    )
    (net (code "140") (name "Net-(Q11-E)") (class "Default")
      (node (ref "Q11") (pin "1") (pinfunction "E_1") (pintype "passive"))
      (node (ref "R38") (pin "1") (pinfunction "1_1") (pintype "passive"))
    )
    (net (code "141") (name "Net-(Q12-E)") (class "Default")
      (node (ref "Q12") (pin "1") (pinfunction "E_1") (pintype "passive"))
      (node (ref "R39") (pin "1") (pinfunction "1_1") (pintype "passive"))
    )
    (net (code "142") (name "Net-(Q13-E)") (class "Default")
      (node (ref "Q13") (pin "1") (pinfunction "E_1") (pintype "passive"))
      (node (ref "R40") (pin "1") (pinfunction "1_1") (pintype "passive"))
    )
    (net (code "143") (name "Net-(Q14-E)") (class "Default")
      (node (ref "Q14") (pin "1") (pinfunction "E_1") (pintype "passive"))
      (node (ref "R41") (pin "1") (pinfunction "1_1") (pintype "passive"))
    )
    (net (code "144") (name "Net-(Q15-E)") (class "Default")
      (node (ref "Q15") (pin "1") (pinfunction "E_1") (pintype "passive"))
      (node (ref "R42") (pin "1") (pinfunction "1_1") (pintype "passive"))
    )
    (net (code "145") (name "Net-(Q16-E)") (class "Default")
      (node (ref "Q16") (pin "1") (pinfunction "E_1") (pintype "passive"))
      (node (ref "R43") (pin "1") (pinfunction "1_1") (pintype "passive"))
    )
    (net (code "146") (name "Net-(Q17-E)") (class "Default")
      (node (ref "Q17") (pin "1") (pinfunction "E_1") (pintype "passive"))
      (node (ref "R44") (pin "1") (pinfunction "1_1") (pintype "passive"))
    )
    (net (code "147") (name "Net-(Q18-E)") (class "Default")
      (node (ref "Q18") (pin "1") (pinfunction "E_1") (pintype "passive"))
      (node (ref "R45") (pin "2") (pinfunction "2_2") (pintype "passive"))
    )
    (net (code "148") (name "Net-(Q20-E)") (class "Default")
      (node (ref "Q20") (pin "1") (pinfunction "E_1") (pintype "passive"))
      (node (ref "R47") (pin "1") (pinfunction "1_1") (pintype "passive"))
    )
    (net (code "149") (name "Net-(Q21-E)") (class "Default")
      (node (ref "Q21") (pin "1") (pinfunction "E_1") (pintype "passive"))
      (node (ref "R48") (pin "1") (pinfunction "1_1") (pintype "passive"))
    )
    (net (code "150") (name "Net-(Q22-E)") (class "Default")
      (node (ref "Q22") (pin "1") (pinfunction "E_1") (pintype "passive"))
      (node (ref "R49") (pin "1") (pinfunction "1_1") (pintype "passive"))
    )
    (net (code "151") (name "Net-(Q23-E)") (class "Default")
      (node (ref "Q23") (pin "1") (pinfunction "E_1") (pintype "passive"))
      (node (ref "R50") (pin "1") (pinfunction "1_1") (pintype "passive"))
    )
    (net (code "152") (name "Net-(Q24-E)") (class "Default")
      (node (ref "Q24") (pin "1") (pinfunction "E_1") (pintype "passive"))
      (node (ref "R51") (pin "1") (pinfunction "1_1") (pintype "passive"))
    )
    (net (code "153") (name "Net-(Q25-E)") (class "Default")
      (node (ref "Q25") (pin "1") (pinfunction "E_1") (pintype "passive"))
      (node (ref "R52") (pin "1") (pinfunction "1_1") (pintype "passive"))
    )
    (net (code "154") (name "Net-(Q26-E)") (class "Default")
      (node (ref "Q26") (pin "1") (pinfunction "E_1") (pintype "passive"))
      (node (ref "R53") (pin "1") (pinfunction "1_1") (pintype "passive"))
    )
    (net (code "155") (name "Net-(Q27-E)") (class "Default")
      (node (ref "Q27") (pin "1") (pinfunction "E_1") (pintype "passive"))
      (node (ref "R54") (pin "1") (pinfunction "1_1") (pintype "passive"))
    )
    (net (code "156") (name "Net-(Q28-E)") (class "Default")
      (node (ref "Q28") (pin "1") (pinfunction "E_1") (pintype "passive"))
      (node (ref "R55") (pin "1") (pinfunction "1_1") (pintype "passive"))
    )
    (net (code "157") (name "Net-(Q29-E)") (class "Default")
      (node (ref "Q29") (pin "1") (pinfunction "E_1") (pintype "passive"))
      (node (ref "R56") (pin "1") (pinfunction "1_1") (pintype "passive"))
    )
    (net (code "158") (name "Net-(Q30-E)") (class "Default")
      (node (ref "Q30") (pin "1") (pinfunction "E_1") (pintype "passive"))
      (node (ref "R57") (pin "1") (pinfunction "1_1") (pintype "passive"))
    )
    (net (code "159") (name "Net-(Q31-E)") (class "Default")
      (node (ref "Q31") (pin "1") (pinfunction "E_1") (pintype "passive"))
      (node (ref "R58") (pin "1") (pinfunction "1_1") (pintype "passive"))
    )
    (net (code "160") (name "Net-(Q32-E)") (class "Default")
      (node (ref "Q32") (pin "1") (pinfunction "E_1") (pintype "passive"))
      (node (ref "R61") (pin "1") (pinfunction "1_1") (pintype "passive"))
    )
    (net (code "161") (name "Net-(Q33-E)") (class "Default")
      (node (ref "Q33") (pin "1") (pinfunction "E_1") (pintype "passive"))
      (node (ref "R62") (pin "1") (pinfunction "1_1") (pintype "passive"))
    )
    (net (code "162") (name "Net-(Q34-E)") (class "Default")
      (node (ref "Q34") (pin "1") (pinfunction "E_1") (pintype "passive"))
      (node (ref "R63") (pin "1") (pinfunction "1_1") (pintype "passive"))
    )
    (net (code "163") (name "Net-(Q35-E)") (class "Default")
      (node (ref "Q35") (pin "1") (pinfunction "E_1") (pintype "passive"))
      (node (ref "R64") (pin "1") (pinfunction "1_1") (pintype "passive"))
    )
    (net (code "164") (name "Net-(Q36-E)") (class "Default")
      (node (ref "Q36") (pin "1") (pinfunction "E_1") (pintype "passive"))
      (node (ref "R65") (pin "1") (pinfunction "1_1") (pintype "passive"))
    )
    (net (code "165") (name "Net-(Q37-E)") (class "Default")
      (node (ref "Q37") (pin "1") (pinfunction "E_1") (pintype "passive"))
      (node (ref "R66") (pin "1") (pinfunction "1_1") (pintype "passive"))
    )
    (net (code "166") (name "Net-(Q38-E)") (class "Default")
      (node (ref "Q38") (pin "1") (pinfunction "E_1") (pintype "passive"))
      (node (ref "R67") (pin "1") (pinfunction "1_1") (pintype "passive"))
    )
    (net (code "167") (name "Net-(Q39-E)") (class "Default")
      (node (ref "Q39") (pin "1") (pinfunction "E_1") (pintype "passive"))
      (node (ref "R68") (pin "1") (pinfunction "1_1") (pintype "passive"))
    )
    (net (code "168") (name "Net-(Q40-E)") (class "Default")
      (node (ref "Q40") (pin "1") (pinfunction "E_1") (pintype "passive"))
      (node (ref "R71") (pin "1") (pinfunction "1_1") (pintype "passive"))
    )
    (net (code "169") (name "Net-(Q41-E)") (class "Default")
      (node (ref "Q41") (pin "1") (pinfunction "E_1") (pintype "passive"))
      (node (ref "R72") (pin "1") (pinfunction "1_1") (pintype "passive"))
    )
    (net (code "170") (name "Net-(Q42-E)") (class "Default")
      (node (ref "Q42") (pin "1") (pinfunction "E_1") (pintype "passive"))
      (node (ref "R73") (pin "1") (pinfunction "1_1") (pintype "passive"))
    )
    (net (code "171") (name "Net-(Q43-E)") (class "Default")
      (node (ref "Q43") (pin "1") (pinfunction "E_1") (pintype "passive"))
      (node (ref "R74") (pin "1") (pinfunction "1_1") (pintype "passive"))
    )
    (net (code "172") (name "Net-(U*1-QH')") (class "Default")
      (node (ref "U*1") (pin "9") (pinfunction "QH'_9") (pintype "passive"))
      (node (ref "U*2") (pin "14") (pinfunction "SI_14") (pintype "passive"))
    )
    (net (code "173") (name "Net-(U*2-QH')") (class "Default")
      (node (ref "U*2") (pin "9") (pinfunction "QH'_9") (pintype "passive"))
      (node (ref "U*3") (pin "14") (pinfunction "SI_14") (pintype "passive"))
    )
    (net (code "174") (name "Net-(U*3-QH')") (class "Default")
      (node (ref "U*3") (pin "9") (pinfunction "QH'_9") (pintype "passive"))
      (node (ref "U*4") (pin "14") (pinfunction "SI_14") (pintype "passive"))
    )
    (net (code "175") (name "Net-(U*4-QH')") (class "Default")
      (node (ref "U*4") (pin "9") (pinfunction "QH'_9") (pintype "passive"))
      (node (ref "U*5") (pin "14") (pinfunction "SI_14") (pintype "passive"))
    )
    (net (code "176") (name "Net-(U4-VBAT)") (class "Default")
      (node (ref "BAT1") (pin "1") (pinfunction "1_1") (pintype "passive"))
      (node (ref "U4") (pin "14") (pinfunction "VBAT_14") (pintype "passive"))
    )
    (net (code "177") (name "Net-(U5-BOOT0)") (class "Default")
      (node (ref "R8") (pin "2") (pinfunction "2_2") (pintype "passive"))
      (node (ref "U5") (pin "44") (pinfunction "BOOT0_44") (pintype "passive"))
    )
    (net (code "178") (name "Net-(U5-NRST)") (class "Default")
      (node (ref "9") (pin "1") (pinfunction "1_1") (pintype "passive"))
      (node (ref "R10") (pin "1") (pinfunction "1_1") (pintype "passive"))
      (node (ref "U5") (pin "7") (pinfunction "NRST_7") (pintype "passive"))
    )
    (net (code "179") (name "Net-(U5-PB2{slash}BOOT1)") (class "Default")
      (node (ref "R25") (pin "1") (pinfunction "1_1") (pintype "passive"))
      (node (ref "U5") (pin "20") (pinfunction "PB2/BOOT1_20") (pintype "passive"))
    )
    (net (code "180") (name "Net-(U6-C1)") (class "Default")
      (node (ref "C9") (pin "2") (pinfunction "2_2") (pintype "passive"))
      (node (ref "U6") (pin "2") (pinfunction "C1_2") (pintype "passive"))
    )
    (net (code "181") (name "Net-(U6-CSEL)") (class "Default")
      (node (ref "C10") (pin "2") (pinfunction "2_2") (pintype "passive"))
      (node (ref "U6") (pin "3") (pinfunction "CSEL_3") (pintype "passive"))
    )
    (net (code "182") (name "Net-(U6-PAD0)") (class "Default")
      (node (ref "R19") (pin "2") (pinfunction "2_2") (pintype "passive"))
      (node (ref "U6") (pin "4") (pinfunction "PAD0_4") (pintype "passive"))
    )
    (net (code "183") (name "Net-(U6-PAD1)") (class "Default")
      (node (ref "R20") (pin "2") (pinfunction "2_2") (pintype "passive"))
      (node (ref "U6") (pin "5") (pinfunction "PAD1_5") (pintype "passive"))
    )
    (net (code "184") (name "Net-(U6-PAD2)") (class "Default")
      (node (ref "R21") (pin "2") (pinfunction "2_2") (pintype "passive"))
      (node (ref "U6") (pin "6") (pinfunction "PAD2_6") (pintype "passive"))
    )
    (net (code "185") (name "Net-(U6-PAD3)") (class "Default")
      (node (ref "R22") (pin "2") (pinfunction "2_2") (pintype "passive"))
      (node (ref "U6") (pin "7") (pinfunction "PAD3_7") (pintype "passive"))
    )
    (net (code "186") (name "Net-(U6-PAD4)") (class "Default")
      (node (ref "R23") (pin "2") (pinfunction "2_2") (pintype "passive"))
      (node (ref "U6") (pin "8") (pinfunction "PAD4_8") (pintype "passive"))
    )
    (net (code "187") (name "Net-(U6-PAD5)") (class "Default")
      (node (ref "R24") (pin "2") (pinfunction "2_2") (pintype "passive"))
      (node (ref "U6") (pin "9") (pinfunction "PAD5_9") (pintype "passive"))
    )
    (net (code "188") (name "VH") (class "Default")
      (node (ref "P1") (pin "4") (pinfunction "4_4") (pintype "passive"))
      (node (ref "R35") (pin "1") (pinfunction "1_1") (pintype "passive"))
      (node (ref "R36") (pin "1") (pinfunction "1_1") (pintype "passive"))
      (node (ref "R59") (pin "2") (pinfunction "2_2") (pintype "passive"))
      (node (ref "R60") (pin "2") (pinfunction "2_2") (pintype "passive"))
      (node (ref "R69") (pin "2") (pinfunction "2_2") (pintype "passive"))
      (node (ref "R70") (pin "2") (pinfunction "2_2") (pintype "passive"))
    )
    (net (code "189") (name "unconnected-(L4-DOUT-Pad2)") (class "Default")
      (node (ref "L4") (pin "2") (pinfunction "DOUT_2") (pintype "passive"))
    )
    (net (code "190") (name "unconnected-(N1-LP-Pad13)") (class "Default")
      (node (ref "N1") (pin "13") (pinfunction "LP_13") (pintype "passive"))
    )
    (net (code "191") (name "unconnected-(N1-RP-Pad2)") (class "Default")
      (node (ref "N1") (pin "2") (pinfunction "RP_2") (pintype "passive"))
    )
    (net (code "192") (name "unconnected-(N2-LP-Pad13)") (class "Default")
      (node (ref "N2") (pin "13") (pinfunction "LP_13") (pintype "passive"))
    )
    (net (code "193") (name "unconnected-(N2-RP-Pad2)") (class "Default")
      (node (ref "N2") (pin "2") (pinfunction "RP_2") (pintype "passive"))
    )
    (net (code "194") (name "unconnected-(N3-LP-Pad13)") (class "Default")
      (node (ref "N3") (pin "13") (pinfunction "LP_13") (pintype "passive"))
    )
    (net (code "195") (name "unconnected-(N3-RP-Pad2)") (class "Default")
      (node (ref "N3") (pin "2") (pinfunction "RP_2") (pintype "passive"))
    )
    (net (code "196") (name "unconnected-(N4-LP-Pad13)") (class "Default")
      (node (ref "N4") (pin "13") (pinfunction "LP_13") (pintype "passive"))
    )
    (net (code "197") (name "unconnected-(N4-RP-Pad2)") (class "Default")
      (node (ref "N4") (pin "2") (pinfunction "RP_2") (pintype "passive"))
    )
    (net (code "198") (name "unconnected-(U*5-QH'-Pad9)") (class "Default")
      (node (ref "U*5") (pin "9") (pinfunction "QH'_9") (pintype "passive"))
    )
    (net (code "199") (name "unconnected-(U1-Pad2)") (class "Default")
      (node (ref "U1") (pin "2") (pinfunction "2_2") (pintype "passive"))
    )
    (net (code "200") (name "unconnected-(U1-Pad3)") (class "Default")
      (node (ref "U1") (pin "3") (pinfunction "3_3") (pintype "passive"))
    )
    (net (code "201") (name "unconnected-(U3-NC(VCC)-Pad10)") (class "Default")
      (node (ref "U3") (pin "10") (pinfunction "NC(VCC)_10") (pintype "passive"))
    )
    (net (code "202") (name "unconnected-(U3-PIO0-Pad16)") (class "Default")
      (node (ref "U3") (pin "16") (pinfunction "PIO0_16") (pintype "passive"))
    )
    (net (code "203") (name "unconnected-(U3-PIO1-Pad15)") (class "Default")
      (node (ref "U3") (pin "15") (pinfunction "PIO1_15") (pintype "passive"))
    )
    (net (code "204") (name "unconnected-(U3-PIO2-Pad14)") (class "Default")
      (node (ref "U3") (pin "14") (pinfunction "PIO2_14") (pintype "passive"))
    )
    (net (code "205") (name "unconnected-(U3-PIO3-Pad13)") (class "Default")
      (node (ref "U3") (pin "13") (pinfunction "PIO3_13") (pintype "passive"))
    )
    (net (code "206") (name "unconnected-(U3-RESETB-Pad11)") (class "Default")
      (node (ref "U3") (pin "11") (pinfunction "RESETB_11") (pintype "passive"))
    )
    (net (code "207") (name "unconnected-(U3-SPI_CLK-Pad7)") (class "Default")
      (node (ref "U3") (pin "7") (pinfunction "SPI_CLK_7") (pintype "passive"))
    )
    (net (code "208") (name "unconnected-(U3-SPI_CSB-Pad6)") (class "Default")
      (node (ref "U3") (pin "6") (pinfunction "SPI_CSB_6") (pintype "passive"))
    )
    (net (code "209") (name "unconnected-(U3-SPI_MISO-Pad8)") (class "Default")
      (node (ref "U3") (pin "8") (pinfunction "SPI_MISO_8") (pintype "passive"))
    )
    (net (code "210") (name "unconnected-(U3-SPI_MOSI-Pad5)") (class "Default")
      (node (ref "U3") (pin "5") (pinfunction "SPI_MOSI_5") (pintype "passive"))
    )
    (net (code "211") (name "unconnected-(U3-UART_CTS-Pad3)") (class "Default")
      (node (ref "U3") (pin "3") (pinfunction "UART_CTS_3") (pintype "passive"))
    )
    (net (code "212") (name "unconnected-(U3-UART_RTS-Pad1)") (class "Default")
      (node (ref "U3") (pin "1") (pinfunction "UART_RTS_1") (pintype "passive"))
    )
    (net (code "213") (name "unconnected-(U4-32KHz-Pad1)") (class "Default")
      (node (ref "U4") (pin "1") (pinfunction "32KHz_1") (pintype "passive"))
    )
    (net (code "214") (name "unconnected-(U4-RST-Pad4)") (class "Default")
      (node (ref "U4") (pin "4") (pinfunction "RST_4") (pintype "passive"))
    )
    (net (code "215") (name "unconnected-(U5-PA1{slash}USART2_RTS{slash}ADC12_0IN1{slash}TIM2_CH2-Pad11)") (class "Default")
      (node (ref "U5") (pin "11") (pinfunction "PA1/USART2_RTS/ADC12_0IN1/TIM2_CH2_11") (pintype "passive"))
    )
    (net (code "216") (name "unconnected-(U5-PA2{slash}USART2_TX{slash}ADC12_IN2{slash}TIM2_CH3-Pad12)") (class "Default")
      (node (ref "U5") (pin "12") (pinfunction "PA2/USART2_TX/ADC12_IN2/TIM2_CH3_12") (pintype "passive"))
    )
    (net (code "217") (name "unconnected-(U5-PA3{slash}USART2_RX{slash}ADC12_IN3{slash}TIM2_CH4-Pad13)") (class "Default")
      (node (ref "U5") (pin "13") (pinfunction "PA3/USART2_RX/ADC12_IN3/TIM2_CH4_13") (pintype "passive"))
    )
    (net (code "218") (name "unconnected-(U5-PA6{slash}SPI1_MISO{slash}ADC12_IN6{slash}TIM3_CH1{slash}TIM1_BKIN-Pad16)") (class "Default")
      (node (ref "U5") (pin "16") (pinfunction "PA6/SPI1_MISO/ADC12_IN6/TIM3_CH1/TIM1_BKIN_16") (pintype "passive"))
    )
    (net (code "219") (name "unconnected-(U5-PA8{slash}USART1_CK{slash}TIM1_CH1{slash}MCO-Pad29)") (class "Default")
      (node (ref "U5") (pin "29") (pinfunction "PA8/USART1_CK/TIM1_CH1/MCO_29") (pintype "passive+no_connect"))
    )
    (net (code "220") (name "unconnected-(U5-PA9{slash}USART1_TX{slash}TIM1_CH2-Pad30)") (class "Default")
      (node (ref "U5") (pin "30") (pinfunction "PA9/USART1_TX/TIM1_CH2_30") (pintype "passive+no_connect"))
    )
    (net (code "221") (name "unconnected-(U5-PAO{slash}WKUP{slash}USART2_CTS{slash}ADC12_IN0{slash}TIM2_CH1_ETR-Pad10)") (class "Default")
      (node (ref "U5") (pin "10") (pinfunction "PAO/WKUP/USART2_CTS/ADC12_IN0/TIM2_CH1_ETR_10") (pintype "passive"))
    )
    (net (code "222") (name "unconnected-(U5-PB1{slash}ADC12_IN9{slash}TIM3_CH4{slash}TIM1_CH3N-Pad19)") (class "Default")
      (node (ref "U5") (pin "19") (pinfunction "PB1/ADC12_IN9/TIM3_CH4/TIM1_CH3N_19") (pintype "passive"))
    )
    (net (code "223") (name "unconnected-(U5-PB3{slash}JTDO{slash}TIM2_CH2{slash}TRACESWO{slash}SPI1_SCK-Pad39)") (class "Default")
      (node (ref "U5") (pin "39") (pinfunction "PB3/JTDO/TIM2_CH2/TRACESWO/SPI1_SCK_39") (pintype "passive"))
    )
    (net (code "224") (name "unconnected-(U5-PB10{slash}I2C2_SCL{slash}USART3_TX{slash}TIM2_CH3-Pad21)") (class "Default")
      (node (ref "U5") (pin "21") (pinfunction "PB10/I2C2_SCL/USART3_TX/TIM2_CH3_21") (pintype "passive"))
    )
    (net (code "225") (name "unconnected-(U5-PB11{slash}I2C2_SDA{slash}USART3_RX{slash}TIM2_CH4-Pad22)") (class "Default")
      (node (ref "U5") (pin "22") (pinfunction "PB11/I2C2_SDA/USART3_RX/TIM2_CH4_22") (pintype "passive"))
    )
    (net (code "226") (name "unconnected-(U5-PC13{slash}TAMPER-RTC-Pad2)") (class "Default")
      (node (ref "U5") (pin "2") (pinfunction "PC13/TAMPER-RTC_2") (pintype "passive"))
    )
    (net (code "227") (name "unconnected-(U5-PC14{slash}OSC32_IN-Pad3)") (class "Default")
      (node (ref "U5") (pin "3") (pinfunction "PC14/OSC32_IN_3") (pintype "passive"))
    )
    (net (code "228") (name "unconnected-(U5-PC15{slash}OSC32_OUT-Pad4)") (class "Default")
      (node (ref "U5") (pin "4") (pinfunction "PC15/OSC32_OUT_4") (pintype "passive"))
    )
  )
)
